# protoCtrl.net
KiCad netlist of a schematic drawn in EAGLE
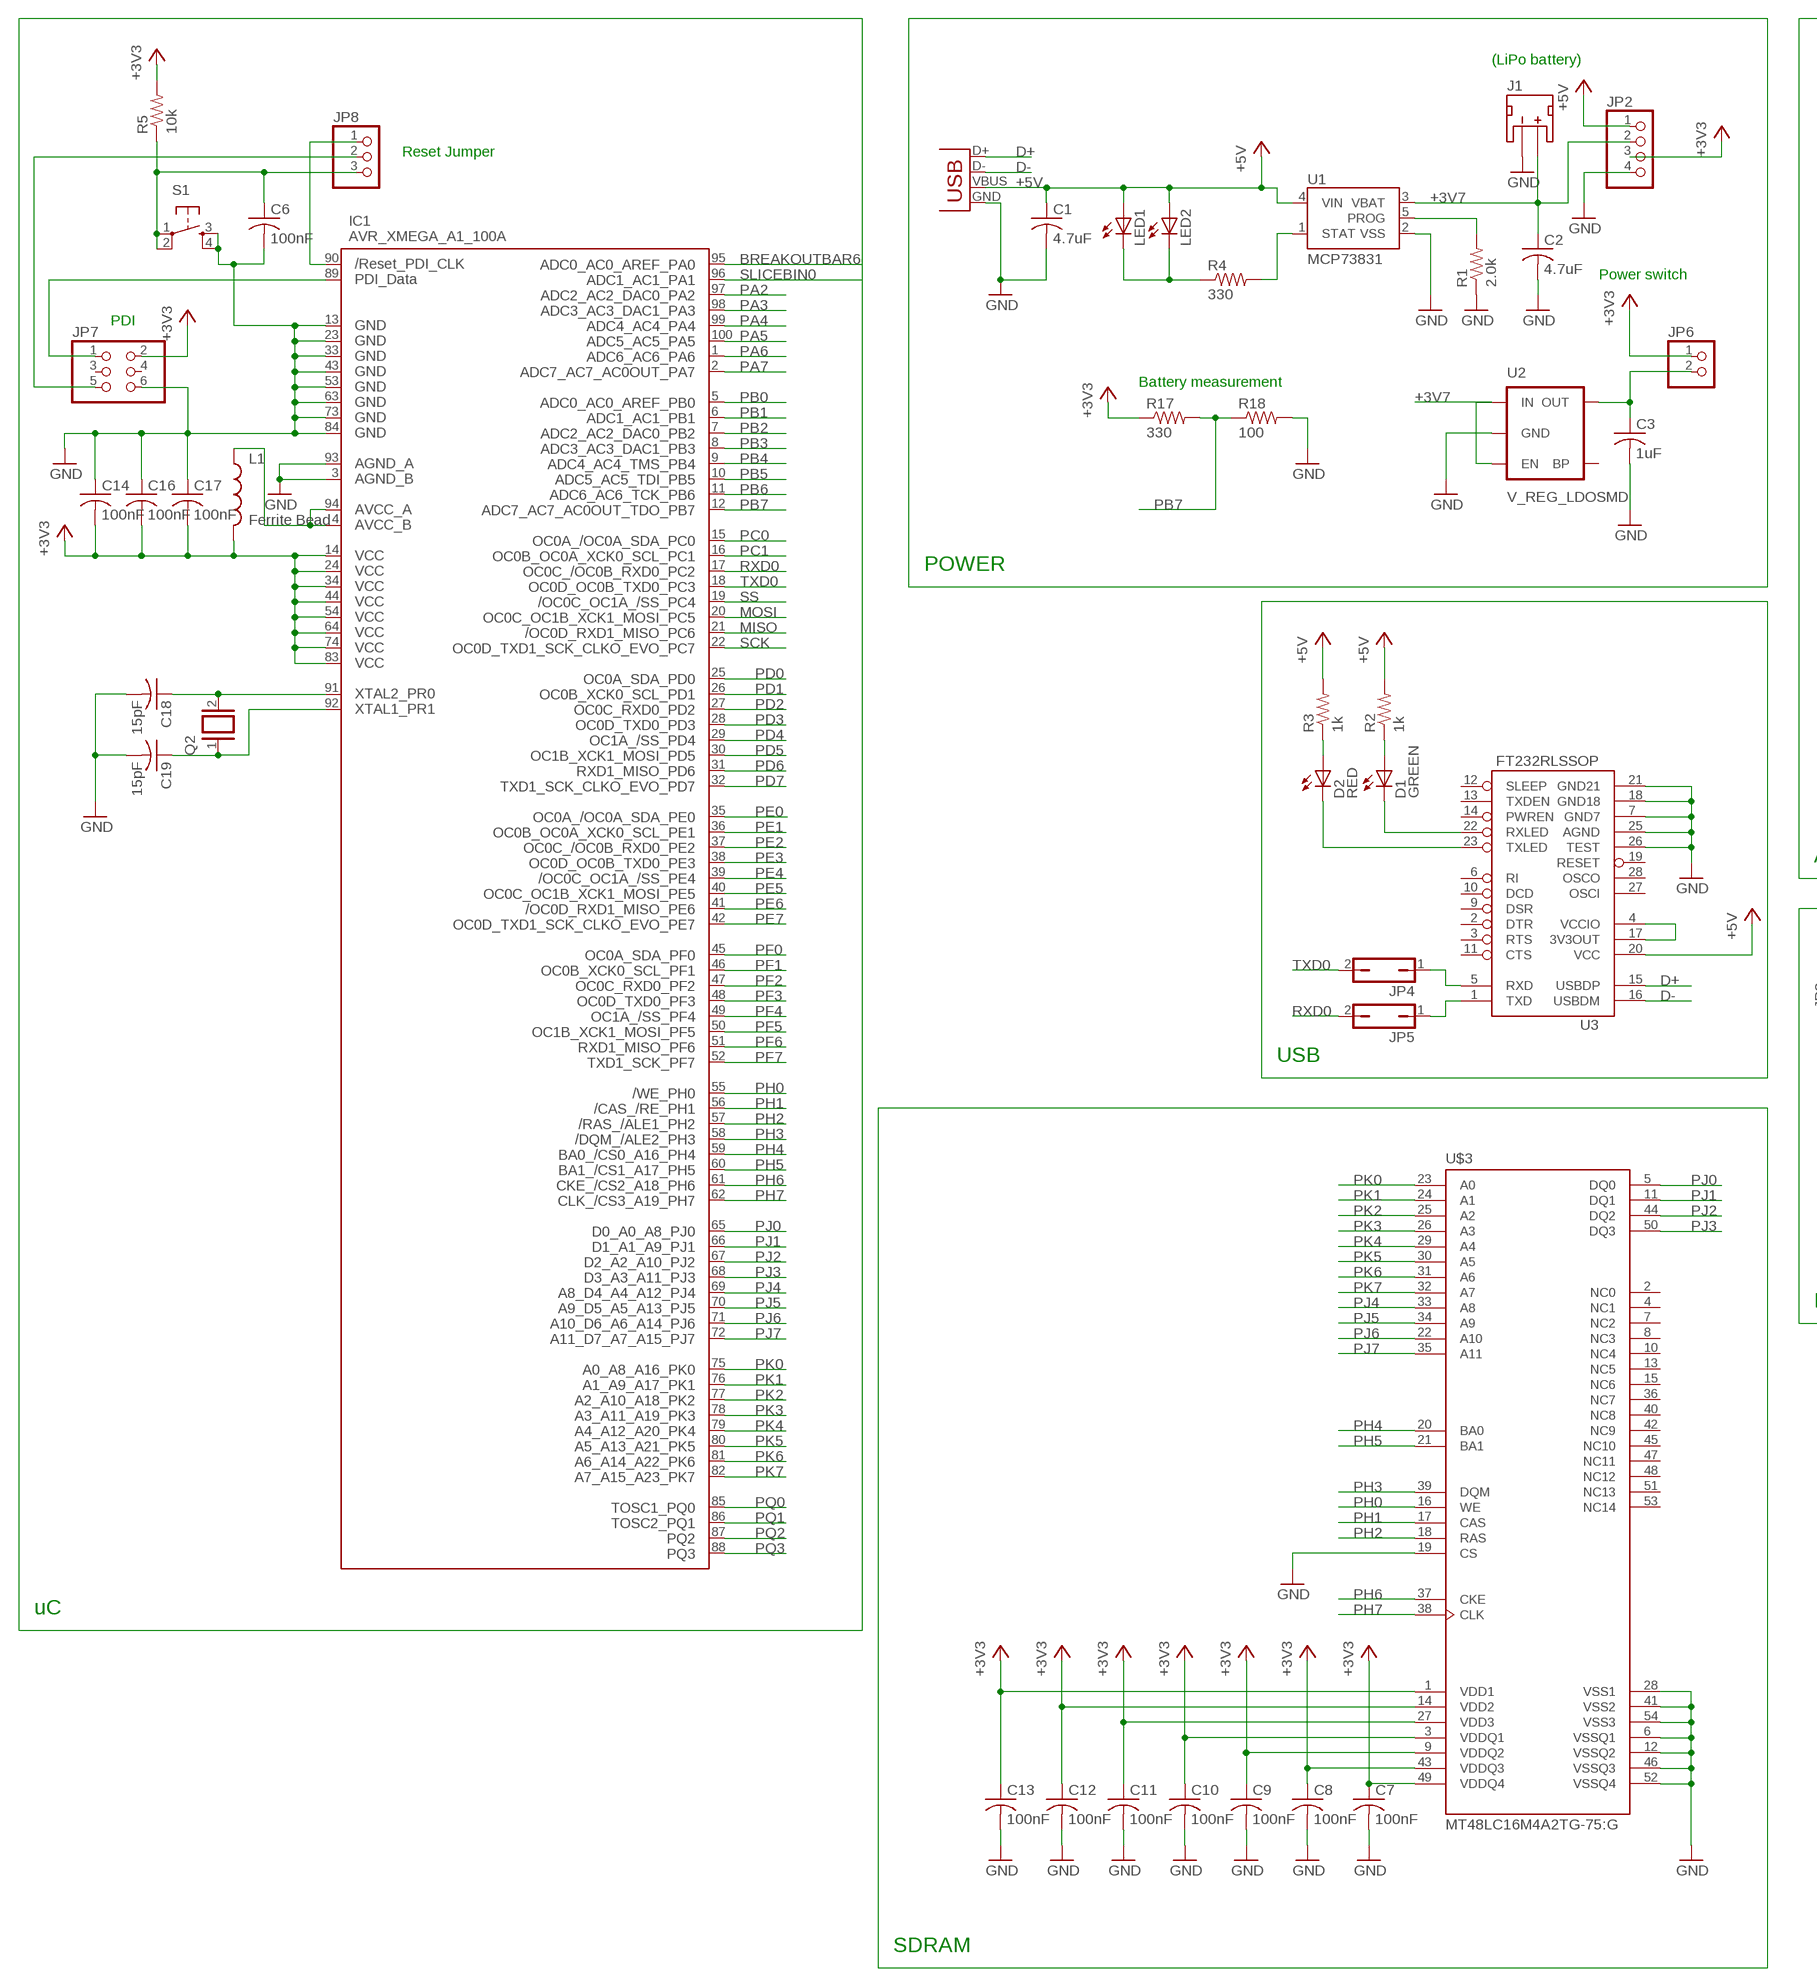
[diagram p0: schematic, sheet 1, part 1 of 2]
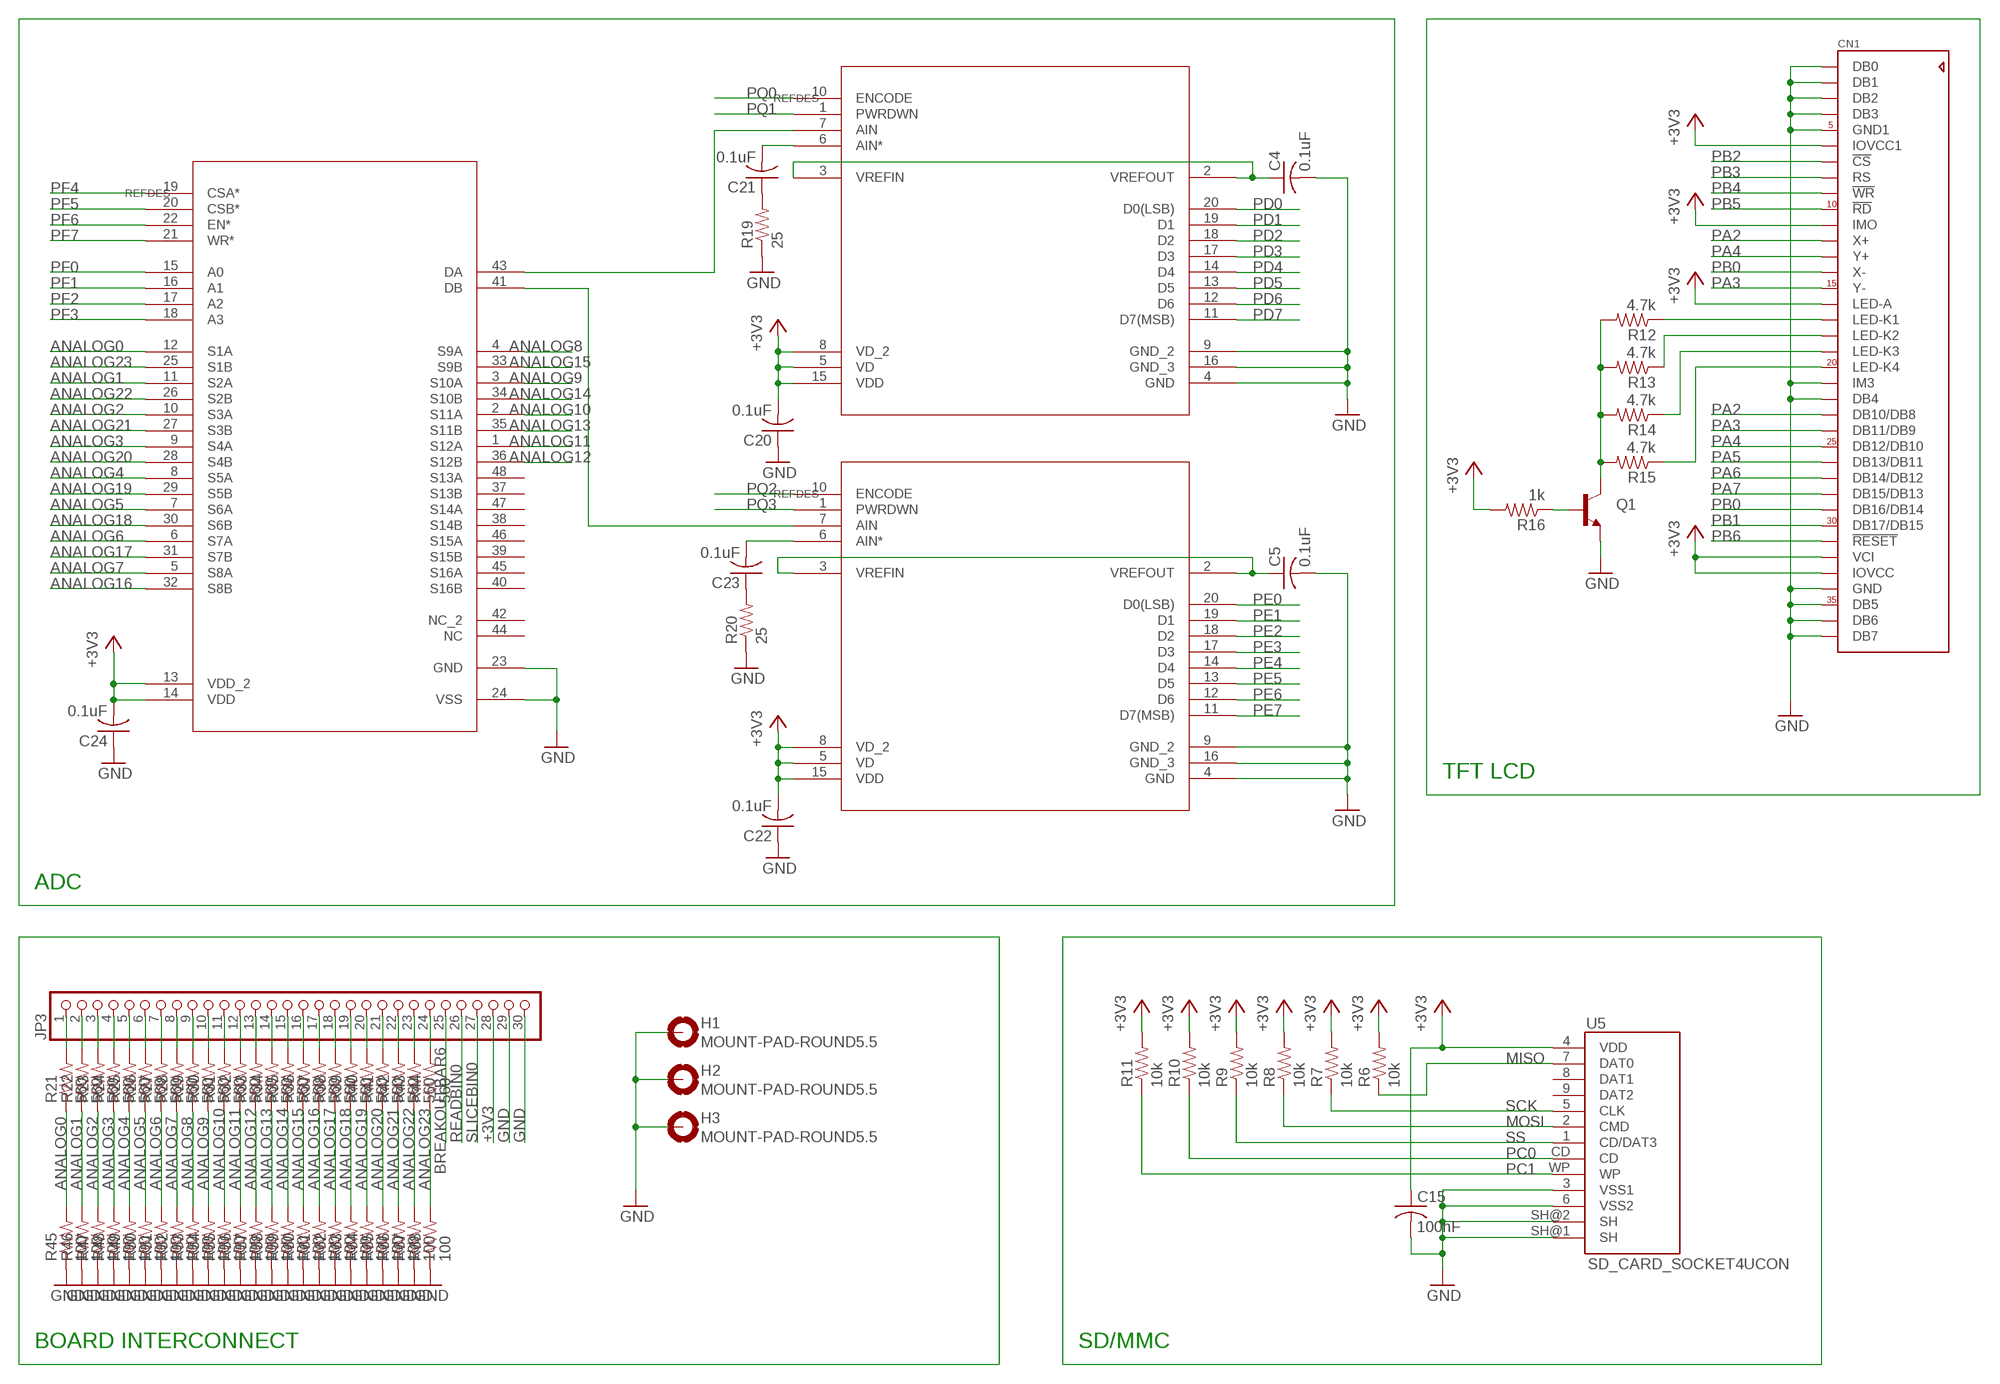
[diagram p1: schematic, sheet 1, part 2 of 2]

(export (version "E")
  (design (tool "Eeschema 10.0.6"))
  (components
    (comp (ref "C1")
      (value "4.7uF")
      (footprint "eagle-import:C0603")
      (libsource (lib "eagle-import") (part "C-USC0603"))
    )
    (comp (ref "C2")
      (value "4.7uF")
      (footprint "eagle-import:C0603")
      (libsource (lib "eagle-import") (part "C-USC0603"))
    )
    (comp (ref "C3")
      (value "1uF")
      (footprint "eagle-import:C0603")
      (libsource (lib "eagle-import") (part "C-USC0603"))
    )
    (comp (ref "C4")
      (value "0.1uF")
      (footprint "eagle-import:C0603")
      (libsource (lib "eagle-import") (part "C-USC0603"))
    )
    (comp (ref "C5")
      (value "0.1uF")
      (footprint "eagle-import:C0603")
      (libsource (lib "eagle-import") (part "C-USC0603"))
    )
    (comp (ref "C6")
      (value "100nF")
      (footprint "eagle-import:C0603")
      (libsource (lib "eagle-import") (part "C-USC0603"))
    )
    (comp (ref "C7")
      (value "100nF")
      (footprint "eagle-import:C0603")
      (libsource (lib "eagle-import") (part "C-USC0603"))
    )
    (comp (ref "C8")
      (value "100nF")
      (footprint "eagle-import:C0603")
      (libsource (lib "eagle-import") (part "C-USC0603"))
    )
    (comp (ref "C9")
      (value "100nF")
      (footprint "eagle-import:C0603")
      (libsource (lib "eagle-import") (part "C-USC0603"))
    )
    (comp (ref "C10")
      (value "100nF")
      (footprint "eagle-import:C0603")
      (libsource (lib "eagle-import") (part "C-USC0603"))
    )
    (comp (ref "C11")
      (value "100nF")
      (footprint "eagle-import:C0603")
      (libsource (lib "eagle-import") (part "C-USC0603"))
    )
    (comp (ref "C12")
      (value "100nF")
      (footprint "eagle-import:C0603")
      (libsource (lib "eagle-import") (part "C-USC0603"))
    )
    (comp (ref "C13")
      (value "100nF")
      (footprint "eagle-import:C0603")
      (libsource (lib "eagle-import") (part "C-USC0603"))
    )
    (comp (ref "C14")
      (value "100nF")
      (footprint "eagle-import:C0603")
      (libsource (lib "eagle-import") (part "C-USC0603"))
    )
    (comp (ref "C15")
      (value "100nF")
      (footprint "eagle-import:C0603")
      (libsource (lib "eagle-import") (part "C-USC0603"))
    )
    (comp (ref "C16")
      (value "100nF")
      (footprint "eagle-import:C0603")
      (libsource (lib "eagle-import") (part "C-USC0603"))
    )
    (comp (ref "C17")
      (value "100nF")
      (footprint "eagle-import:C0603")
      (libsource (lib "eagle-import") (part "C-USC0603"))
    )
    (comp (ref "C18")
      (value "15pF")
      (footprint "eagle-import:C0603")
      (libsource (lib "eagle-import") (part "resistor_C-USC0603"))
    )
    (comp (ref "C19")
      (value "15pF")
      (footprint "eagle-import:C0603")
      (libsource (lib "eagle-import") (part "resistor_C-USC0603"))
    )
    (comp (ref "C20")
      (value "0.1uF")
      (footprint "eagle-import:C0603")
      (libsource (lib "eagle-import") (part "C-USC0603"))
    )
    (comp (ref "C21")
      (value "0.1uF")
      (footprint "eagle-import:C0603")
      (libsource (lib "eagle-import") (part "C-USC0603"))
    )
    (comp (ref "C22")
      (value "0.1uF")
      (footprint "eagle-import:C0603")
      (libsource (lib "eagle-import") (part "C-USC0603"))
    )
    (comp (ref "C23")
      (value "0.1uF")
      (footprint "eagle-import:C0603")
      (libsource (lib "eagle-import") (part "C-USC0603"))
    )
    (comp (ref "C24")
      (value "0.1uF")
      (footprint "eagle-import:C0603")
      (libsource (lib "eagle-import") (part "C-USC0603"))
    )
    (comp (ref "CN1")
      (value "ILI9325_LCD1.0MM")
      (footprint "eagle-import:ILI9325_28INCH_TS")
      (libsource (lib "eagle-import") (part "ILI9325_LCD1.0MM"))
    )
    (comp (ref "D1")
      (value "GREEN")
      (footprint "eagle-import:LED-0603")
      (libsource (lib "eagle-import") (part "LED-GREEN0603"))
    )
    (comp (ref "D2")
      (value "RED")
      (footprint "eagle-import:LED-0603")
      (libsource (lib "eagle-import") (part "LED-RED0603"))
    )
    (comp (ref "H1")
      (value "MOUNT-PAD-ROUND5.5")
      (footprint "eagle-import:5,5-PAD")
      (libsource (lib "eagle-import") (part "MOUNT-PAD-ROUND5.5"))
    )
    (comp (ref "H2")
      (value "MOUNT-PAD-ROUND5.5")
      (footprint "eagle-import:5,5-PAD")
      (libsource (lib "eagle-import") (part "MOUNT-PAD-ROUND5.5"))
    )
    (comp (ref "H3")
      (value "MOUNT-PAD-ROUND5.5")
      (footprint "eagle-import:5,5-PAD")
      (libsource (lib "eagle-import") (part "MOUNT-PAD-ROUND5.5"))
    )
    (comp (ref "IC1")
      (value "AVR_XMEGA_A1_100A")
      (footprint "eagle-import:TQFP100")
      (libsource (lib "eagle-import") (part "AVR_XMEGA_A1_100A"))
    )
    (comp (ref "J1")
      (value "JST_2MM_MALE")
      (footprint "eagle-import:JST-2-SMD")
      (libsource (lib "eagle-import") (part "JST_2MM_MALE"))
    )
    (comp (ref "JP1")
      (value "USBSMD")
      (footprint "eagle-import:USB-MINIB")
      (libsource (lib "eagle-import") (part "USBSMD"))
    )
    (comp (ref "JP2")
      (value "PINHD-1X4")
      (footprint "eagle-import:1X04")
      (libsource (lib "eagle-import") (part "PINHD-1X4"))
    )
    (comp (ref "JP3")
      (value "PINHD-1X30")
      (footprint "eagle-import:1X30")
      (libsource (lib "eagle-import") (part "PINHD-1X30"))
    )
    (comp (ref "JP4")
      (value "JP1Q")
      (footprint "eagle-import:JP1")
      (libsource (lib "eagle-import") (part "JP1Q"))
    )
    (comp (ref "JP5")
      (value "JP1Q")
      (footprint "eagle-import:JP1")
      (libsource (lib "eagle-import") (part "JP1Q"))
    )
    (comp (ref "JP6")
      (value "PINHD-1X2")
      (footprint "eagle-import:1X02")
      (libsource (lib "eagle-import") (part "PINHD-1X2"))
    )
    (comp (ref "JP7")
      (value "PINHD-2X3")
      (footprint "eagle-import:2X03")
      (libsource (lib "eagle-import") (part "PINHD-2X3"))
    )
    (comp (ref "JP8")
      (value "PINHD-1X3")
      (footprint "eagle-import:1X03")
      (libsource (lib "eagle-import") (part "PINHD-1X3"))
    )
    (comp (ref "L1")
      (value "Ferrite Bead")
      (footprint "eagle-import:0603")
      (libsource (lib "eagle-import") (part "INDUCTOR0603"))
    )
    (comp (ref "LED1")
      (value "LED1206")
      (footprint "eagle-import:LED-1206")
      (libsource (lib "eagle-import") (part "LED1206"))
    )
    (comp (ref "LED2")
      (value "LED3MM")
      (footprint "eagle-import:LED3MM")
      (libsource (lib "eagle-import") (part "LED3MM"))
    )
    (comp (ref "Q1")
      (value "TRANSISTOR_NPN\"")
      (footprint "eagle-import:SOT223")
      (libsource (lib "eagle-import") (part "TRANSISTOR_NPN{dblquote}"))
    )
    (comp (ref "Q2")
      (value "XTAL/S")
      (footprint "eagle-import:QS")
      (libsource (lib "eagle-import") (part "XTAL/S"))
    )
    (comp (ref "R1")
      (value "2.0k")
      (footprint "eagle-import:0402-RES")
      (libsource (lib "eagle-import") (part "2.0KOHM1/10W5%(0603)"))
    )
    (comp (ref "R2")
      (value "1k")
      (footprint "eagle-import:0402-RES")
      (libsource (lib "eagle-import") (part "1K-1%"))
    )
    (comp (ref "R3")
      (value "1k")
      (footprint "eagle-import:0402-RES")
      (libsource (lib "eagle-import") (part "1K-1%"))
    )
    (comp (ref "R4")
      (value "330")
      (footprint "eagle-import:0402-RES")
      (libsource (lib "eagle-import") (part "330OHM1/10W1%(0603)"))
    )
    (comp (ref "R5")
      (value "10k")
      (footprint "eagle-import:0402-RES")
      (fields (field (name "PROD_ID") "RES-08296"))
      (libsource (lib "eagle-import") (part "2.0KOHM1/10W5%(0603)"))
    )
    (comp (ref "R6")
      (value "10k")
      (footprint "eagle-import:0402-RES")
      (fields (field (name "PROD_ID") "RES-08296"))
      (libsource (lib "eagle-import") (part "2.0KOHM1/10W5%(0603)"))
    )
    (comp (ref "R7")
      (value "10k")
      (footprint "eagle-import:0402-RES")
      (fields (field (name "PROD_ID") "RES-08296"))
      (libsource (lib "eagle-import") (part "2.0KOHM1/10W5%(0603)"))
    )
    (comp (ref "R8")
      (value "10k")
      (footprint "eagle-import:0402-RES")
      (fields (field (name "PROD_ID") "RES-08296"))
      (libsource (lib "eagle-import") (part "2.0KOHM1/10W5%(0603)"))
    )
    (comp (ref "R9")
      (value "10k")
      (footprint "eagle-import:0402-RES")
      (fields (field (name "PROD_ID") "RES-08296"))
      (libsource (lib "eagle-import") (part "2.0KOHM1/10W5%(0603)"))
    )
    (comp (ref "R10")
      (value "10k")
      (footprint "eagle-import:0402-RES")
      (fields (field (name "PROD_ID") "RES-08296"))
      (libsource (lib "eagle-import") (part "2.0KOHM1/10W5%(0603)"))
    )
    (comp (ref "R11")
      (value "10k")
      (footprint "eagle-import:0402-RES")
      (fields (field (name "PROD_ID") "RES-08296"))
      (libsource (lib "eagle-import") (part "2.0KOHM1/10W5%(0603)"))
    )
    (comp (ref "R12")
      (value "4.7k")
      (footprint "eagle-import:0402-RES")
      (fields (field (name "PROD_ID") "RES-08296"))
      (libsource (lib "eagle-import") (part "2.0KOHM1/10W5%(0603)"))
    )
    (comp (ref "R13")
      (value "4.7k")
      (footprint "eagle-import:0402-RES")
      (fields (field (name "PROD_ID") "RES-08296"))
      (libsource (lib "eagle-import") (part "2.0KOHM1/10W5%(0603)"))
    )
    (comp (ref "R14")
      (value "4.7k")
      (footprint "eagle-import:0402-RES")
      (fields (field (name "PROD_ID") "RES-08296"))
      (libsource (lib "eagle-import") (part "2.0KOHM1/10W5%(0603)"))
    )
    (comp (ref "R15")
      (value "4.7k")
      (footprint "eagle-import:0402-RES")
      (fields (field (name "PROD_ID") "RES-08296"))
      (libsource (lib "eagle-import") (part "2.0KOHM1/10W5%(0603)"))
    )
    (comp (ref "R16")
      (value "1k")
      (footprint "eagle-import:0402-RES")
      (fields (field (name "PROD_ID") "RES-08296"))
      (libsource (lib "eagle-import") (part "2.0KOHM1/10W5%(0603)"))
    )
    (comp (ref "R17")
      (value "330")
      (footprint "eagle-import:0402-RES")
      (fields (field (name "PROD_ID") "RES-00818"))
      (libsource (lib "eagle-import") (part "330OHM1/10W1%(0603)"))
    )
    (comp (ref "R18")
      (value "100")
      (footprint "eagle-import:0402-RES")
      (fields (field (name "PROD_ID") "RES-00818"))
      (libsource (lib "eagle-import") (part "330OHM1/10W1%(0603)"))
    )
    (comp (ref "R19")
      (value "25")
      (footprint "eagle-import:0402-RES")
      (fields (field (name "PROD_ID") "RES-00818"))
      (libsource (lib "eagle-import") (part "330OHM1/10W1%(0603)"))
    )
    (comp (ref "R20")
      (value "25")
      (footprint "eagle-import:0402-RES")
      (fields (field (name "PROD_ID") "RES-00818"))
      (libsource (lib "eagle-import") (part "330OHM1/10W1%(0603)"))
    )
    (comp (ref "R21")
      (value "560")
      (footprint "eagle-import:0402-RES")
      (fields (field (name "PROD_ID") "RES-00818"))
      (libsource (lib "eagle-import") (part "330OHM1/10W1%(0603)"))
    )
    (comp (ref "R22")
      (value "560")
      (footprint "eagle-import:0402-RES")
      (fields (field (name "PROD_ID") "RES-00818"))
      (libsource (lib "eagle-import") (part "330OHM1/10W1%(0603)"))
    )
    (comp (ref "R23")
      (value "560")
      (footprint "eagle-import:0402-RES")
      (fields (field (name "PROD_ID") "RES-00818"))
      (libsource (lib "eagle-import") (part "330OHM1/10W1%(0603)"))
    )
    (comp (ref "R24")
      (value "560")
      (footprint "eagle-import:0402-RES")
      (fields (field (name "PROD_ID") "RES-00818"))
      (libsource (lib "eagle-import") (part "330OHM1/10W1%(0603)"))
    )
    (comp (ref "R25")
      (value "560")
      (footprint "eagle-import:0402-RES")
      (fields (field (name "PROD_ID") "RES-00818"))
      (libsource (lib "eagle-import") (part "330OHM1/10W1%(0603)"))
    )
    (comp (ref "R26")
      (value "560")
      (footprint "eagle-import:0402-RES")
      (fields (field (name "PROD_ID") "RES-00818"))
      (libsource (lib "eagle-import") (part "330OHM1/10W1%(0603)"))
    )
    (comp (ref "R27")
      (value "560")
      (footprint "eagle-import:0402-RES")
      (fields (field (name "PROD_ID") "RES-00818"))
      (libsource (lib "eagle-import") (part "330OHM1/10W1%(0603)"))
    )
    (comp (ref "R28")
      (value "560")
      (footprint "eagle-import:0402-RES")
      (fields (field (name "PROD_ID") "RES-00818"))
      (libsource (lib "eagle-import") (part "330OHM1/10W1%(0603)"))
    )
    (comp (ref "R29")
      (value "560")
      (footprint "eagle-import:0402-RES")
      (fields (field (name "PROD_ID") "RES-00818"))
      (libsource (lib "eagle-import") (part "330OHM1/10W1%(0603)"))
    )
    (comp (ref "R30")
      (value "560")
      (footprint "eagle-import:0402-RES")
      (fields (field (name "PROD_ID") "RES-00818"))
      (libsource (lib "eagle-import") (part "330OHM1/10W1%(0603)"))
    )
    (comp (ref "R31")
      (value "560")
      (footprint "eagle-import:0402-RES")
      (fields (field (name "PROD_ID") "RES-00818"))
      (libsource (lib "eagle-import") (part "330OHM1/10W1%(0603)"))
    )
    (comp (ref "R32")
      (value "560")
      (footprint "eagle-import:0402-RES")
      (fields (field (name "PROD_ID") "RES-00818"))
      (libsource (lib "eagle-import") (part "330OHM1/10W1%(0603)"))
    )
    (comp (ref "R33")
      (value "560")
      (footprint "eagle-import:0402-RES")
      (fields (field (name "PROD_ID") "RES-00818"))
      (libsource (lib "eagle-import") (part "330OHM1/10W1%(0603)"))
    )
    (comp (ref "R34")
      (value "560")
      (footprint "eagle-import:0402-RES")
      (fields (field (name "PROD_ID") "RES-00818"))
      (libsource (lib "eagle-import") (part "330OHM1/10W1%(0603)"))
    )
    (comp (ref "R35")
      (value "560")
      (footprint "eagle-import:0402-RES")
      (fields (field (name "PROD_ID") "RES-00818"))
      (libsource (lib "eagle-import") (part "330OHM1/10W1%(0603)"))
    )
    (comp (ref "R36")
      (value "560")
      (footprint "eagle-import:0402-RES")
      (fields (field (name "PROD_ID") "RES-00818"))
      (libsource (lib "eagle-import") (part "330OHM1/10W1%(0603)"))
    )
    (comp (ref "R37")
      (value "560")
      (footprint "eagle-import:0402-RES")
      (fields (field (name "PROD_ID") "RES-00818"))
      (libsource (lib "eagle-import") (part "330OHM1/10W1%(0603)"))
    )
    (comp (ref "R38")
      (value "560")
      (footprint "eagle-import:0402-RES")
      (fields (field (name "PROD_ID") "RES-00818"))
      (libsource (lib "eagle-import") (part "330OHM1/10W1%(0603)"))
    )
    (comp (ref "R39")
      (value "560")
      (footprint "eagle-import:0402-RES")
      (fields (field (name "PROD_ID") "RES-00818"))
      (libsource (lib "eagle-import") (part "330OHM1/10W1%(0603)"))
    )
    (comp (ref "R40")
      (value "560")
      (footprint "eagle-import:0402-RES")
      (fields (field (name "PROD_ID") "RES-00818"))
      (libsource (lib "eagle-import") (part "330OHM1/10W1%(0603)"))
    )
    (comp (ref "R41")
      (value "560")
      (footprint "eagle-import:0402-RES")
      (fields (field (name "PROD_ID") "RES-00818"))
      (libsource (lib "eagle-import") (part "330OHM1/10W1%(0603)"))
    )
    (comp (ref "R42")
      (value "560")
      (footprint "eagle-import:0402-RES")
      (fields (field (name "PROD_ID") "RES-00818"))
      (libsource (lib "eagle-import") (part "330OHM1/10W1%(0603)"))
    )
    (comp (ref "R43")
      (value "560")
      (footprint "eagle-import:0402-RES")
      (fields (field (name "PROD_ID") "RES-00818"))
      (libsource (lib "eagle-import") (part "330OHM1/10W1%(0603)"))
    )
    (comp (ref "R44")
      (value "560")
      (footprint "eagle-import:0402-RES")
      (fields (field (name "PROD_ID") "RES-00818"))
      (libsource (lib "eagle-import") (part "330OHM1/10W1%(0603)"))
    )
    (comp (ref "R45")
      (value "100")
      (footprint "eagle-import:0402-RES")
      (fields (field (name "PROD_ID") "RES-00818"))
      (libsource (lib "eagle-import") (part "330OHM1/10W1%(0603)"))
    )
    (comp (ref "R46")
      (value "100")
      (footprint "eagle-import:0402-RES")
      (fields (field (name "PROD_ID") "RES-00818"))
      (libsource (lib "eagle-import") (part "330OHM1/10W1%(0603)"))
    )
    (comp (ref "R47")
      (value "100")
      (footprint "eagle-import:0402-RES")
      (fields (field (name "PROD_ID") "RES-00818"))
      (libsource (lib "eagle-import") (part "330OHM1/10W1%(0603)"))
    )
    (comp (ref "R48")
      (value "100")
      (footprint "eagle-import:0402-RES")
      (fields (field (name "PROD_ID") "RES-00818"))
      (libsource (lib "eagle-import") (part "330OHM1/10W1%(0603)"))
    )
    (comp (ref "R49")
      (value "100")
      (footprint "eagle-import:0402-RES")
      (fields (field (name "PROD_ID") "RES-00818"))
      (libsource (lib "eagle-import") (part "330OHM1/10W1%(0603)"))
    )
    (comp (ref "R50")
      (value "100")
      (footprint "eagle-import:0402-RES")
      (fields (field (name "PROD_ID") "RES-00818"))
      (libsource (lib "eagle-import") (part "330OHM1/10W1%(0603)"))
    )
    (comp (ref "R51")
      (value "100")
      (footprint "eagle-import:0402-RES")
      (fields (field (name "PROD_ID") "RES-00818"))
      (libsource (lib "eagle-import") (part "330OHM1/10W1%(0603)"))
    )
    (comp (ref "R52")
      (value "100")
      (footprint "eagle-import:0402-RES")
      (fields (field (name "PROD_ID") "RES-00818"))
      (libsource (lib "eagle-import") (part "330OHM1/10W1%(0603)"))
    )
    (comp (ref "R53")
      (value "100")
      (footprint "eagle-import:0402-RES")
      (fields (field (name "PROD_ID") "RES-00818"))
      (libsource (lib "eagle-import") (part "330OHM1/10W1%(0603)"))
    )
    (comp (ref "R54")
      (value "100")
      (footprint "eagle-import:0402-RES")
      (fields (field (name "PROD_ID") "RES-00818"))
      (libsource (lib "eagle-import") (part "330OHM1/10W1%(0603)"))
    )
    (comp (ref "R55")
      (value "100")
      (footprint "eagle-import:0402-RES")
      (fields (field (name "PROD_ID") "RES-00818"))
      (libsource (lib "eagle-import") (part "330OHM1/10W1%(0603)"))
    )
    (comp (ref "R56")
      (value "100")
      (footprint "eagle-import:0402-RES")
      (fields (field (name "PROD_ID") "RES-00818"))
      (libsource (lib "eagle-import") (part "330OHM1/10W1%(0603)"))
    )
    (comp (ref "R57")
      (value "100")
      (footprint "eagle-import:0402-RES")
      (fields (field (name "PROD_ID") "RES-00818"))
      (libsource (lib "eagle-import") (part "330OHM1/10W1%(0603)"))
    )
    (comp (ref "R58")
      (value "100")
      (footprint "eagle-import:0402-RES")
      (fields (field (name "PROD_ID") "RES-00818"))
      (libsource (lib "eagle-import") (part "330OHM1/10W1%(0603)"))
    )
    (comp (ref "R59")
      (value "100")
      (footprint "eagle-import:0402-RES")
      (fields (field (name "PROD_ID") "RES-00818"))
      (libsource (lib "eagle-import") (part "330OHM1/10W1%(0603)"))
    )
    (comp (ref "R60")
      (value "100")
      (footprint "eagle-import:0402-RES")
      (fields (field (name "PROD_ID") "RES-00818"))
      (libsource (lib "eagle-import") (part "330OHM1/10W1%(0603)"))
    )
    (comp (ref "R61")
      (value "100")
      (footprint "eagle-import:0402-RES")
      (fields (field (name "PROD_ID") "RES-00818"))
      (libsource (lib "eagle-import") (part "330OHM1/10W1%(0603)"))
    )
    (comp (ref "R62")
      (value "100")
      (footprint "eagle-import:0402-RES")
      (fields (field (name "PROD_ID") "RES-00818"))
      (libsource (lib "eagle-import") (part "330OHM1/10W1%(0603)"))
    )
    (comp (ref "R63")
      (value "100")
      (footprint "eagle-import:0402-RES")
      (fields (field (name "PROD_ID") "RES-00818"))
      (libsource (lib "eagle-import") (part "330OHM1/10W1%(0603)"))
    )
    (comp (ref "R64")
      (value "100")
      (footprint "eagle-import:0402-RES")
      (fields (field (name "PROD_ID") "RES-00818"))
      (libsource (lib "eagle-import") (part "330OHM1/10W1%(0603)"))
    )
    (comp (ref "R65")
      (value "100")
      (footprint "eagle-import:0402-RES")
      (fields (field (name "PROD_ID") "RES-00818"))
      (libsource (lib "eagle-import") (part "330OHM1/10W1%(0603)"))
    )
    (comp (ref "R66")
      (value "100")
      (footprint "eagle-import:0402-RES")
      (fields (field (name "PROD_ID") "RES-00818"))
      (libsource (lib "eagle-import") (part "330OHM1/10W1%(0603)"))
    )
    (comp (ref "R67")
      (value "100")
      (footprint "eagle-import:0402-RES")
      (fields (field (name "PROD_ID") "RES-00818"))
      (libsource (lib "eagle-import") (part "330OHM1/10W1%(0603)"))
    )
    (comp (ref "R68")
      (value "100")
      (footprint "eagle-import:0402-RES")
      (fields (field (name "PROD_ID") "RES-00818"))
      (libsource (lib "eagle-import") (part "330OHM1/10W1%(0603)"))
    )
    (comp (ref "S1")
      (value "TAC_SWITCHPTH")
      (footprint "eagle-import:TACTILE-PTH")
      (libsource (lib "eagle-import") (part "TAC_SWITCHPTH"))
    )
    (comp (ref "U$3")
      (value "MT48LC16M4A2TG-75:G")
      (footprint "eagle-import:TSOP54-400")
      (libsource (lib "eagle-import") (part "MT48LC16M4A2TG-75{colon}G"))
    )
    (comp (ref "U1")
      (value "MCP73831")
      (footprint "eagle-import:SOT23-5")
      (libsource (lib "eagle-import") (part "MCP73831"))
    )
    (comp (ref "U2")
      (value "V_REG_LDOSMD")
      (footprint "eagle-import:SOT23-5")
      (libsource (lib "eagle-import") (part "V_REG_LDOSMD"))
    )
    (comp (ref "U3")
      (value "FT232RLSSOP")
      (footprint "eagle-import:SSOP28DB")
      (libsource (lib "eagle-import") (part "FT232RLSSOP"))
    )
    (comp (ref "U4")
      (value "ADG726BSUZ")
      (footprint "eagle-import:SU_48")
      (libsource (lib "eagle-import") (part "ADG726BSUZ"))
    )
    (comp (ref "U5")
      (value "SD_CARD_SOCKET4UCON")
      (footprint "eagle-import:SDCARD_4UCONN")
      (libsource (lib "eagle-import") (part "SD_CARD_SOCKET4UCON"))
    )
    (comp (ref "U6")
      (value "AD9283BRSZ-80REAL")
      (footprint "eagle-import:SSOP20")
      (libsource (lib "eagle-import") (part "AD9283BRSZ-80REAL"))
    )
    (comp (ref "U7")
      (value "AD9283BRSZ-80REAL")
      (footprint "eagle-import:SSOP20")
      (libsource (lib "eagle-import") (part "AD9283BRSZ-80REAL"))
    )
  )
  (nets
    (net (code "1") (name "+3V3") (class "Default")
      (node (ref "C10") (pin "1") (pinfunction "1_1") (pintype "passive"))
      (node (ref "C11") (pin "1") (pinfunction "1_1") (pintype "passive"))
      (node (ref "C12") (pin "1") (pinfunction "1_1") (pintype "passive"))
      (node (ref "C13") (pin "1") (pinfunction "1_1") (pintype "passive"))
      (node (ref "C14") (pin "2") (pinfunction "2_2") (pintype "passive"))
      (node (ref "C15") (pin "1") (pinfunction "1_1") (pintype "passive"))
      (node (ref "C16") (pin "2") (pinfunction "2_2") (pintype "passive"))
      (node (ref "C17") (pin "2") (pinfunction "2_2") (pintype "passive"))
      (node (ref "C20") (pin "2") (pinfunction "2_2") (pintype "passive"))
      (node (ref "C22") (pin "2") (pinfunction "2_2") (pintype "passive"))
      (node (ref "C24") (pin "2") (pinfunction "2_2") (pintype "passive"))
      (node (ref "C7") (pin "1") (pinfunction "1_1") (pintype "passive"))
      (node (ref "C8") (pin "1") (pinfunction "1_1") (pintype "passive"))
      (node (ref "C9") (pin "1") (pinfunction "1_1") (pintype "passive"))
      (node (ref "CN1") (pin "11") (pinfunction "IMO_11") (pintype "passive"))
      (node (ref "CN1") (pin "16") (pinfunction "LED-A_16") (pintype "passive"))
      (node (ref "CN1") (pin "32") (pinfunction "VCI_32") (pintype "power_in"))
      (node (ref "CN1") (pin "33") (pinfunction "IOVCC_33") (pintype "power_in"))
      (node (ref "CN1") (pin "6") (pinfunction "IOVCC1_6") (pintype "power_in"))
      (node (ref "IC1") (pin "14") (pinfunction "VCC1_14") (pintype "bidirectional"))
      (node (ref "IC1") (pin "24") (pinfunction "VCC2_24") (pintype "bidirectional"))
      (node (ref "IC1") (pin "34") (pinfunction "VCC3_34") (pintype "bidirectional"))
      (node (ref "IC1") (pin "44") (pinfunction "VCC4_44") (pintype "bidirectional"))
      (node (ref "IC1") (pin "54") (pinfunction "VCC5_54") (pintype "bidirectional"))
      (node (ref "IC1") (pin "64") (pinfunction "VCC6_64") (pintype "bidirectional"))
      (node (ref "IC1") (pin "74") (pinfunction "VCC7_74") (pintype "bidirectional"))
      (node (ref "IC1") (pin "83") (pinfunction "VCC8_83") (pintype "bidirectional"))
      (node (ref "JP2") (pin "3") (pinfunction "3_3") (pintype "passive"))
      (node (ref "JP3") (pin "28") (pinfunction "28_28") (pintype "passive"))
      (node (ref "JP6") (pin "1") (pinfunction "1_1") (pintype "passive"))
      (node (ref "JP7") (pin "2") (pinfunction "2_2") (pintype "passive"))
      (node (ref "L1") (pin "2") (pinfunction "2_2") (pintype "passive"))
      (node (ref "R10") (pin "2") (pinfunction "2_2") (pintype "passive"))
      (node (ref "R11") (pin "2") (pinfunction "2_2") (pintype "passive"))
      (node (ref "R16") (pin "2") (pinfunction "2_2") (pintype "passive"))
      (node (ref "R17") (pin "1") (pinfunction "1_1") (pintype "passive"))
      (node (ref "R5") (pin "2") (pinfunction "2_2") (pintype "passive"))
      (node (ref "R6") (pin "2") (pinfunction "2_2") (pintype "passive"))
      (node (ref "R7") (pin "2") (pinfunction "2_2") (pintype "passive"))
      (node (ref "R8") (pin "2") (pinfunction "2_2") (pintype "passive"))
      (node (ref "R9") (pin "2") (pinfunction "2_2") (pintype "passive"))
      (node (ref "U$3") (pin "1") (pinfunction "VDD1_1") (pintype "power_in"))
      (node (ref "U$3") (pin "14") (pinfunction "VDD2_14") (pintype "power_in"))
      (node (ref "U$3") (pin "27") (pinfunction "VDD3_27") (pintype "power_in"))
      (node (ref "U$3") (pin "3") (pinfunction "VDDQ1_3") (pintype "power_in"))
      (node (ref "U$3") (pin "43") (pinfunction "VDDQ3_43") (pintype "power_in"))
      (node (ref "U$3") (pin "49") (pinfunction "VDDQ4_49") (pintype "power_in"))
      (node (ref "U$3") (pin "9") (pinfunction "VDDQ2_9") (pintype "power_in"))
      (node (ref "U4") (pin "13") (pinfunction "VDD_2_13") (pintype "passive"))
      (node (ref "U4") (pin "14") (pinfunction "VDD_14") (pintype "passive"))
      (node (ref "U5") (pin "4") (pinfunction "VDD_4") (pintype "power_in"))
      (node (ref "U6") (pin "15") (pinfunction "VDD_15") (pintype "passive"))
      (node (ref "U6") (pin "5") (pinfunction "VD_5") (pintype "passive"))
      (node (ref "U6") (pin "8") (pinfunction "VD_2_8") (pintype "passive"))
      (node (ref "U7") (pin "15") (pinfunction "VDD_15") (pintype "passive"))
      (node (ref "U7") (pin "5") (pinfunction "VD_5") (pintype "passive"))
      (node (ref "U7") (pin "8") (pinfunction "VD_2_8") (pintype "passive"))
    )
    (net (code "2") (name "+5V") (class "Default")
      (node (ref "C1") (pin "1") (pinfunction "1_1") (pintype "passive"))
      (node (ref "JP1") (pin "VBUS") (pinfunction "VBUS_VBUS") (pintype "bidirectional"))
      (node (ref "JP2") (pin "1") (pinfunction "1_1") (pintype "passive"))
      (node (ref "LED1") (pin "A") (pinfunction "A_A") (pintype "passive"))
      (node (ref "LED2") (pin "A") (pinfunction "A_A") (pintype "passive"))
      (node (ref "R2") (pin "2") (pinfunction "2_2") (pintype "passive"))
      (node (ref "R3") (pin "2") (pinfunction "2_2") (pintype "passive"))
      (node (ref "U1") (pin "4") (pinfunction "VIN_4") (pintype "power_in"))
      (node (ref "U3") (pin "20") (pinfunction "VCC_20") (pintype "power_in"))
    )
    (net (code "3") (name "/+3V7") (class "Default")
      (node (ref "C2") (pin "1") (pinfunction "1_1") (pintype "passive"))
      (node (ref "J1") (pin "2") (pinfunction "+_2") (pintype "bidirectional"))
      (node (ref "JP2") (pin "2") (pinfunction "2_2") (pintype "passive"))
      (node (ref "U1") (pin "3") (pinfunction "VBAT_3") (pintype "power_in"))
      (node (ref "U2") (pin "1") (pinfunction "IN_1") (pintype "input"))
      (node (ref "U2") (pin "3") (pinfunction "EN_3") (pintype "input"))
    )
    (net (code "4") (name "/ANALOG0") (class "Default")
      (node (ref "R21") (pin "1") (pinfunction "1_1") (pintype "passive"))
      (node (ref "R45") (pin "2") (pinfunction "2_2") (pintype "passive"))
      (node (ref "U4") (pin "12") (pinfunction "S1A_12") (pintype "passive"))
    )
    (net (code "5") (name "/ANALOG1") (class "Default")
      (node (ref "R22") (pin "1") (pinfunction "1_1") (pintype "passive"))
      (node (ref "R46") (pin "2") (pinfunction "2_2") (pintype "passive"))
      (node (ref "U4") (pin "11") (pinfunction "S2A_11") (pintype "passive"))
    )
    (net (code "6") (name "/ANALOG2") (class "Default")
      (node (ref "R23") (pin "1") (pinfunction "1_1") (pintype "passive"))
      (node (ref "R47") (pin "2") (pinfunction "2_2") (pintype "passive"))
      (node (ref "U4") (pin "10") (pinfunction "S3A_10") (pintype "passive"))
    )
    (net (code "7") (name "/ANALOG3") (class "Default")
      (node (ref "R24") (pin "1") (pinfunction "1_1") (pintype "passive"))
      (node (ref "R48") (pin "2") (pinfunction "2_2") (pintype "passive"))
      (node (ref "U4") (pin "9") (pinfunction "S4A_9") (pintype "passive"))
    )
    (net (code "8") (name "/ANALOG4") (class "Default")
      (node (ref "R25") (pin "1") (pinfunction "1_1") (pintype "passive"))
      (node (ref "R49") (pin "2") (pinfunction "2_2") (pintype "passive"))
      (node (ref "U4") (pin "8") (pinfunction "S5A_8") (pintype "passive"))
    )
    (net (code "9") (name "/ANALOG5") (class "Default")
      (node (ref "R26") (pin "1") (pinfunction "1_1") (pintype "passive"))
      (node (ref "R50") (pin "2") (pinfunction "2_2") (pintype "passive"))
      (node (ref "U4") (pin "7") (pinfunction "S6A_7") (pintype "passive"))
    )
    (net (code "10") (name "/ANALOG6") (class "Default")
      (node (ref "R27") (pin "1") (pinfunction "1_1") (pintype "passive"))
      (node (ref "R51") (pin "2") (pinfunction "2_2") (pintype "passive"))
      (node (ref "U4") (pin "6") (pinfunction "S7A_6") (pintype "passive"))
    )
    (net (code "11") (name "/ANALOG7") (class "Default")
      (node (ref "R28") (pin "1") (pinfunction "1_1") (pintype "passive"))
      (node (ref "R52") (pin "2") (pinfunction "2_2") (pintype "passive"))
      (node (ref "U4") (pin "5") (pinfunction "S8A_5") (pintype "passive"))
    )
    (net (code "12") (name "/ANALOG8") (class "Default")
      (node (ref "R29") (pin "1") (pinfunction "1_1") (pintype "passive"))
      (node (ref "R53") (pin "2") (pinfunction "2_2") (pintype "passive"))
      (node (ref "U4") (pin "4") (pinfunction "S9A_4") (pintype "passive"))
    )
    (net (code "13") (name "/ANALOG9") (class "Default")
      (node (ref "R30") (pin "1") (pinfunction "1_1") (pintype "passive"))
      (node (ref "R54") (pin "2") (pinfunction "2_2") (pintype "passive"))
      (node (ref "U4") (pin "3") (pinfunction "S10A_3") (pintype "passive"))
    )
    (net (code "14") (name "/ANALOG10") (class "Default")
      (node (ref "R31") (pin "1") (pinfunction "1_1") (pintype "passive"))
      (node (ref "R55") (pin "2") (pinfunction "2_2") (pintype "passive"))
      (node (ref "U4") (pin "2") (pinfunction "S11A_2") (pintype "passive"))
    )
    (net (code "15") (name "/ANALOG11") (class "Default")
      (node (ref "R32") (pin "1") (pinfunction "1_1") (pintype "passive"))
      (node (ref "R56") (pin "2") (pinfunction "2_2") (pintype "passive"))
      (node (ref "U4") (pin "1") (pinfunction "S12A_1") (pintype "passive"))
    )
    (net (code "16") (name "/ANALOG12") (class "Default")
      (node (ref "R33") (pin "1") (pinfunction "1_1") (pintype "passive"))
      (node (ref "R57") (pin "2") (pinfunction "2_2") (pintype "passive"))
      (node (ref "U4") (pin "36") (pinfunction "S12B_36") (pintype "passive"))
    )
    (net (code "17") (name "/ANALOG13") (class "Default")
      (node (ref "R34") (pin "1") (pinfunction "1_1") (pintype "passive"))
      (node (ref "R58") (pin "2") (pinfunction "2_2") (pintype "passive"))
      (node (ref "U4") (pin "35") (pinfunction "S11B_35") (pintype "passive"))
    )
    (net (code "18") (name "/ANALOG14") (class "Default")
      (node (ref "R35") (pin "1") (pinfunction "1_1") (pintype "passive"))
      (node (ref "R59") (pin "2") (pinfunction "2_2") (pintype "passive"))
      (node (ref "U4") (pin "34") (pinfunction "S10B_34") (pintype "passive"))
    )
    (net (code "19") (name "/ANALOG15") (class "Default")
      (node (ref "R36") (pin "1") (pinfunction "1_1") (pintype "passive"))
      (node (ref "R60") (pin "2") (pinfunction "2_2") (pintype "passive"))
      (node (ref "U4") (pin "33") (pinfunction "S9B_33") (pintype "passive"))
    )
    (net (code "20") (name "/ANALOG16") (class "Default")
      (node (ref "R37") (pin "1") (pinfunction "1_1") (pintype "passive"))
      (node (ref "R61") (pin "2") (pinfunction "2_2") (pintype "passive"))
      (node (ref "U4") (pin "32") (pinfunction "S8B_32") (pintype "passive"))
    )
    (net (code "21") (name "/ANALOG17") (class "Default")
      (node (ref "R38") (pin "1") (pinfunction "1_1") (pintype "passive"))
      (node (ref "R62") (pin "2") (pinfunction "2_2") (pintype "passive"))
      (node (ref "U4") (pin "31") (pinfunction "S7B_31") (pintype "passive"))
    )
    (net (code "22") (name "/ANALOG18") (class "Default")
      (node (ref "R39") (pin "1") (pinfunction "1_1") (pintype "passive"))
      (node (ref "R63") (pin "2") (pinfunction "2_2") (pintype "passive"))
      (node (ref "U4") (pin "30") (pinfunction "S6B_30") (pintype "passive"))
    )
    (net (code "23") (name "/ANALOG19") (class "Default")
      (node (ref "R40") (pin "1") (pinfunction "1_1") (pintype "passive"))
      (node (ref "R64") (pin "2") (pinfunction "2_2") (pintype "passive"))
      (node (ref "U4") (pin "29") (pinfunction "S5B_29") (pintype "passive"))
    )
    (net (code "24") (name "/ANALOG20") (class "Default")
      (node (ref "R41") (pin "1") (pinfunction "1_1") (pintype "passive"))
      (node (ref "R65") (pin "2") (pinfunction "2_2") (pintype "passive"))
      (node (ref "U4") (pin "28") (pinfunction "S4B_28") (pintype "passive"))
    )
    (net (code "25") (name "/ANALOG21") (class "Default")
      (node (ref "R42") (pin "1") (pinfunction "1_1") (pintype "passive"))
      (node (ref "R66") (pin "2") (pinfunction "2_2") (pintype "passive"))
      (node (ref "U4") (pin "27") (pinfunction "S3B_27") (pintype "passive"))
    )
    (net (code "26") (name "/ANALOG22") (class "Default")
      (node (ref "R43") (pin "1") (pinfunction "1_1") (pintype "passive"))
      (node (ref "R67") (pin "2") (pinfunction "2_2") (pintype "passive"))
      (node (ref "U4") (pin "26") (pinfunction "S2B_26") (pintype "passive"))
    )
    (net (code "27") (name "/ANALOG23") (class "Default")
      (node (ref "R44") (pin "1") (pinfunction "1_1") (pintype "passive"))
      (node (ref "R68") (pin "2") (pinfunction "2_2") (pintype "passive"))
      (node (ref "U4") (pin "25") (pinfunction "S1B_25") (pintype "passive"))
    )
    (net (code "28") (name "/BREAKOUTBAR6") (class "Default")
      (node (ref "IC1") (pin "95") (pinfunction "PA0_95") (pintype "bidirectional"))
      (node (ref "JP3") (pin "25") (pinfunction "25_25") (pintype "passive"))
    )
    (net (code "29") (name "/D+") (class "Default")
      (node (ref "JP1") (pin "D+") (pinfunction "D+_D+") (pintype "bidirectional"))
      (node (ref "U3") (pin "15") (pinfunction "USBDP_15") (pintype "bidirectional"))
    )
    (net (code "30") (name "/D-") (class "Default")
      (node (ref "JP1") (pin "D-") (pinfunction "D-_D-") (pintype "bidirectional"))
      (node (ref "U3") (pin "16") (pinfunction "USBDM_16") (pintype "bidirectional"))
    )
    (net (code "31") (name "/MISO") (class "Default")
      (node (ref "IC1") (pin "21") (pinfunction "PC6_21") (pintype "bidirectional"))
      (node (ref "R6") (pin "1") (pinfunction "1_1") (pintype "passive"))
      (node (ref "U5") (pin "7") (pinfunction "DAT0_7") (pintype "bidirectional"))
    )
    (net (code "32") (name "/MOSI") (class "Default")
      (node (ref "IC1") (pin "20") (pinfunction "PC5_20") (pintype "bidirectional"))
      (node (ref "R8") (pin "1") (pinfunction "1_1") (pintype "passive"))
      (node (ref "U5") (pin "2") (pinfunction "CMD_2") (pintype "bidirectional"))
    )
    (net (code "33") (name "/PA2") (class "Default")
      (node (ref "CN1") (pin "12") (pinfunction "X+_12") (pintype "passive"))
      (node (ref "CN1") (pin "23") (pinfunction "DB10/DB8_23") (pintype "passive"))
      (node (ref "IC1") (pin "97") (pinfunction "PA2_97") (pintype "bidirectional"))
    )
    (net (code "34") (name "/PA3") (class "Default")
      (node (ref "CN1") (pin "15") (pinfunction "Y-_15") (pintype "passive"))
      (node (ref "CN1") (pin "24") (pinfunction "DB11/DB9_24") (pintype "passive"))
      (node (ref "IC1") (pin "98") (pinfunction "PA3_98") (pintype "bidirectional"))
    )
    (net (code "35") (name "/PA4") (class "Default")
      (node (ref "CN1") (pin "13") (pinfunction "Y+_13") (pintype "passive"))
      (node (ref "CN1") (pin "25") (pinfunction "DB12/DB10_25") (pintype "passive"))
      (node (ref "IC1") (pin "99") (pinfunction "PA4_99") (pintype "bidirectional"))
    )
    (net (code "36") (name "/PA5") (class "Default")
      (node (ref "CN1") (pin "26") (pinfunction "DB13/DB11_26") (pintype "passive"))
      (node (ref "IC1") (pin "100") (pinfunction "PA5_100") (pintype "bidirectional"))
    )
    (net (code "37") (name "/PA6") (class "Default")
      (node (ref "CN1") (pin "27") (pinfunction "DB14/DB12_27") (pintype "passive"))
      (node (ref "IC1") (pin "1") (pinfunction "PA6_1") (pintype "bidirectional"))
    )
    (net (code "38") (name "/PA7") (class "Default")
      (node (ref "CN1") (pin "28") (pinfunction "DB15/DB13_28") (pintype "passive"))
      (node (ref "IC1") (pin "2") (pinfunction "PA7_2") (pintype "bidirectional"))
    )
    (net (code "39") (name "/PB0") (class "Default")
      (node (ref "CN1") (pin "14") (pinfunction "X-_14") (pintype "passive"))
      (node (ref "CN1") (pin "29") (pinfunction "DB16/DB14_29") (pintype "passive"))
      (node (ref "IC1") (pin "5") (pinfunction "PB0_5") (pintype "bidirectional"))
    )
    (net (code "40") (name "/PB1") (class "Default")
      (node (ref "CN1") (pin "30") (pinfunction "DB17/DB15_30") (pintype "passive"))
      (node (ref "IC1") (pin "6") (pinfunction "PB1_6") (pintype "bidirectional"))
    )
    (net (code "41") (name "/PB2") (class "Default")
      (node (ref "CN1") (pin "7") (pinfunction "~{CS}_7") (pintype "passive"))
      (node (ref "IC1") (pin "7") (pinfunction "PB2_7") (pintype "bidirectional"))
    )
    (net (code "42") (name "/PB3") (class "Default")
      (node (ref "CN1") (pin "8") (pinfunction "RS_8") (pintype "passive"))
      (node (ref "IC1") (pin "8") (pinfunction "PB3_8") (pintype "bidirectional"))
    )
    (net (code "43") (name "/PB4") (class "Default")
      (node (ref "CN1") (pin "9") (pinfunction "~{WR}_9") (pintype "passive"))
      (node (ref "IC1") (pin "9") (pinfunction "PB4_9") (pintype "bidirectional"))
    )
    (net (code "44") (name "/PB5") (class "Default")
      (node (ref "CN1") (pin "10") (pinfunction "~{RD}_10") (pintype "passive"))
      (node (ref "IC1") (pin "10") (pinfunction "PB5_10") (pintype "bidirectional"))
    )
    (net (code "45") (name "/PB6") (class "Default")
      (node (ref "CN1") (pin "31") (pinfunction "~{RESET}_31") (pintype "passive"))
      (node (ref "IC1") (pin "11") (pinfunction "PB6_11") (pintype "bidirectional"))
    )
    (net (code "46") (name "/PB7") (class "Default")
      (node (ref "IC1") (pin "12") (pinfunction "PB7_12") (pintype "bidirectional"))
      (node (ref "R17") (pin "2") (pinfunction "2_2") (pintype "passive"))
      (node (ref "R18") (pin "1") (pinfunction "1_1") (pintype "passive"))
    )
    (net (code "47") (name "/PC0") (class "Default")
      (node (ref "IC1") (pin "15") (pinfunction "PC0_15") (pintype "bidirectional"))
      (node (ref "R10") (pin "1") (pinfunction "1_1") (pintype "passive"))
      (node (ref "U5") (pin "CD") (pinfunction "CD_CD") (pintype "bidirectional"))
    )
    (net (code "48") (name "/PC1") (class "Default")
      (node (ref "IC1") (pin "16") (pinfunction "PC1_16") (pintype "bidirectional"))
      (node (ref "R11") (pin "1") (pinfunction "1_1") (pintype "passive"))
      (node (ref "U5") (pin "WP") (pinfunction "WP_WP") (pintype "bidirectional"))
    )
    (net (code "49") (name "/PD0") (class "Default")
      (node (ref "IC1") (pin "25") (pinfunction "PD0_25") (pintype "bidirectional"))
      (node (ref "U6") (pin "20") (pinfunction "D0(LSB)_20") (pintype "passive"))
    )
    (net (code "50") (name "/PD1") (class "Default")
      (node (ref "IC1") (pin "26") (pinfunction "PD1_26") (pintype "bidirectional"))
      (node (ref "U6") (pin "19") (pinfunction "D1_19") (pintype "passive"))
    )
    (net (code "51") (name "/PD2") (class "Default")
      (node (ref "IC1") (pin "27") (pinfunction "PD2_27") (pintype "bidirectional"))
      (node (ref "U6") (pin "18") (pinfunction "D2_18") (pintype "passive"))
    )
    (net (code "52") (name "/PD3") (class "Default")
      (node (ref "IC1") (pin "28") (pinfunction "PD3_28") (pintype "bidirectional"))
      (node (ref "U6") (pin "17") (pinfunction "D3_17") (pintype "passive"))
    )
    (net (code "53") (name "/PD4") (class "Default")
      (node (ref "IC1") (pin "29") (pinfunction "PD4_29") (pintype "bidirectional"))
      (node (ref "U6") (pin "14") (pinfunction "D4_14") (pintype "passive"))
    )
    (net (code "54") (name "/PD5") (class "Default")
      (node (ref "IC1") (pin "30") (pinfunction "PD5_30") (pintype "bidirectional"))
      (node (ref "U6") (pin "13") (pinfunction "D5_13") (pintype "passive"))
    )
    (net (code "55") (name "/PD6") (class "Default")
      (node (ref "IC1") (pin "31") (pinfunction "PD6_31") (pintype "bidirectional"))
      (node (ref "U6") (pin "12") (pinfunction "D6_12") (pintype "passive"))
    )
    (net (code "56") (name "/PD7") (class "Default")
      (node (ref "IC1") (pin "32") (pinfunction "PD7_32") (pintype "bidirectional"))
      (node (ref "U6") (pin "11") (pinfunction "D7(MSB)_11") (pintype "passive"))
    )
    (net (code "57") (name "/PE0") (class "Default")
      (node (ref "IC1") (pin "35") (pinfunction "PE0_35") (pintype "bidirectional"))
      (node (ref "U7") (pin "20") (pinfunction "D0(LSB)_20") (pintype "passive"))
    )
    (net (code "58") (name "/PE1") (class "Default")
      (node (ref "IC1") (pin "36") (pinfunction "PE1_36") (pintype "bidirectional"))
      (node (ref "U7") (pin "19") (pinfunction "D1_19") (pintype "passive"))
    )
    (net (code "59") (name "/PE2") (class "Default")
      (node (ref "IC1") (pin "37") (pinfunction "PE2_37") (pintype "bidirectional"))
      (node (ref "U7") (pin "18") (pinfunction "D2_18") (pintype "passive"))
    )
    (net (code "60") (name "/PE3") (class "Default")
      (node (ref "IC1") (pin "38") (pinfunction "PE3_38") (pintype "bidirectional"))
      (node (ref "U7") (pin "17") (pinfunction "D3_17") (pintype "passive"))
    )
    (net (code "61") (name "/PE4") (class "Default")
      (node (ref "IC1") (pin "39") (pinfunction "PE4_39") (pintype "bidirectional"))
      (node (ref "U7") (pin "14") (pinfunction "D4_14") (pintype "passive"))
    )
    (net (code "62") (name "/PE5") (class "Default")
      (node (ref "IC1") (pin "40") (pinfunction "PE5_40") (pintype "bidirectional"))
      (node (ref "U7") (pin "13") (pinfunction "D5_13") (pintype "passive"))
    )
    (net (code "63") (name "/PE6") (class "Default")
      (node (ref "IC1") (pin "41") (pinfunction "PE6_41") (pintype "bidirectional"))
      (node (ref "U7") (pin "12") (pinfunction "D6_12") (pintype "passive"))
    )
    (net (code "64") (name "/PE7") (class "Default")
      (node (ref "IC1") (pin "42") (pinfunction "PE7_42") (pintype "bidirectional"))
      (node (ref "U7") (pin "11") (pinfunction "D7(MSB)_11") (pintype "passive"))
    )
    (net (code "65") (name "/PF0") (class "Default")
      (node (ref "IC1") (pin "45") (pinfunction "PF0_45") (pintype "bidirectional"))
      (node (ref "U4") (pin "15") (pinfunction "A0_15") (pintype "passive"))
    )
    (net (code "66") (name "/PF1") (class "Default")
      (node (ref "IC1") (pin "46") (pinfunction "PF1_46") (pintype "bidirectional"))
      (node (ref "U4") (pin "16") (pinfunction "A1_16") (pintype "passive"))
    )
    (net (code "67") (name "/PF2") (class "Default")
      (node (ref "IC1") (pin "47") (pinfunction "PF2_47") (pintype "bidirectional"))
      (node (ref "U4") (pin "17") (pinfunction "A2_17") (pintype "passive"))
    )
    (net (code "68") (name "/PF3") (class "Default")
      (node (ref "IC1") (pin "48") (pinfunction "PF3_48") (pintype "bidirectional"))
      (node (ref "U4") (pin "18") (pinfunction "A3_18") (pintype "passive"))
    )
    (net (code "69") (name "/PF4") (class "Default")
      (node (ref "IC1") (pin "49") (pinfunction "PF4_49") (pintype "bidirectional"))
      (node (ref "U4") (pin "19") (pinfunction "CSA*_19") (pintype "passive"))
    )
    (net (code "70") (name "/PF5") (class "Default")
      (node (ref "IC1") (pin "50") (pinfunction "PF5_50") (pintype "bidirectional"))
      (node (ref "U4") (pin "20") (pinfunction "CSB*_20") (pintype "passive"))
    )
    (net (code "71") (name "/PF6") (class "Default")
      (node (ref "IC1") (pin "51") (pinfunction "PF6_51") (pintype "bidirectional"))
      (node (ref "U4") (pin "22") (pinfunction "EN*_22") (pintype "passive"))
    )
    (net (code "72") (name "/PF7") (class "Default")
      (node (ref "IC1") (pin "52") (pinfunction "PF7_52") (pintype "bidirectional"))
      (node (ref "U4") (pin "21") (pinfunction "WR*_21") (pintype "passive"))
    )
    (net (code "73") (name "/PH0") (class "Default")
      (node (ref "IC1") (pin "55") (pinfunction "PH0_55") (pintype "bidirectional"))
      (node (ref "U$3") (pin "16") (pinfunction "WE_16") (pintype "bidirectional"))
    )
    (net (code "74") (name "/PH1") (class "Default")
      (node (ref "IC1") (pin "56") (pinfunction "PH1_56") (pintype "bidirectional"))
      (node (ref "U$3") (pin "17") (pinfunction "CAS_17") (pintype "bidirectional"))
    )
    (net (code "75") (name "/PH2") (class "Default")
      (node (ref "IC1") (pin "57") (pinfunction "PH2_57") (pintype "bidirectional"))
      (node (ref "U$3") (pin "18") (pinfunction "RAS_18") (pintype "bidirectional"))
    )
    (net (code "76") (name "/PH3") (class "Default")
      (node (ref "IC1") (pin "58") (pinfunction "PH3_58") (pintype "bidirectional"))
      (node (ref "U$3") (pin "39") (pinfunction "DQM_39") (pintype "bidirectional"))
    )
    (net (code "77") (name "/PH4") (class "Default")
      (node (ref "IC1") (pin "59") (pinfunction "PH4_59") (pintype "bidirectional"))
      (node (ref "U$3") (pin "20") (pinfunction "BA0_20") (pintype "bidirectional"))
    )
    (net (code "78") (name "/PH5") (class "Default")
      (node (ref "IC1") (pin "60") (pinfunction "PH5_60") (pintype "bidirectional"))
      (node (ref "U$3") (pin "21") (pinfunction "BA1_21") (pintype "bidirectional"))
    )
    (net (code "79") (name "/PH6") (class "Default")
      (node (ref "IC1") (pin "61") (pinfunction "PH6_61") (pintype "bidirectional"))
      (node (ref "U$3") (pin "37") (pinfunction "CKE_37") (pintype "bidirectional"))
    )
    (net (code "80") (name "/PH7") (class "Default")
      (node (ref "IC1") (pin "62") (pinfunction "PH7_62") (pintype "bidirectional"))
      (node (ref "U$3") (pin "38") (pinfunction "CLK_38") (pintype "bidirectional"))
    )
    (net (code "81") (name "/PJ0") (class "Default")
      (node (ref "IC1") (pin "65") (pinfunction "PJ0_65") (pintype "bidirectional"))
      (node (ref "U$3") (pin "5") (pinfunction "DQ0_5") (pintype "bidirectional"))
    )
    (net (code "82") (name "/PJ1") (class "Default")
      (node (ref "IC1") (pin "66") (pinfunction "PJ1_66") (pintype "bidirectional"))
      (node (ref "U$3") (pin "11") (pinfunction "DQ1_11") (pintype "bidirectional"))
    )
    (net (code "83") (name "/PJ2") (class "Default")
      (node (ref "IC1") (pin "67") (pinfunction "PJ2_67") (pintype "bidirectional"))
      (node (ref "U$3") (pin "44") (pinfunction "DQ2_44") (pintype "bidirectional"))
    )
    (net (code "84") (name "/PJ3") (class "Default")
      (node (ref "IC1") (pin "68") (pinfunction "PJ3_68") (pintype "bidirectional"))
      (node (ref "U$3") (pin "50") (pinfunction "DQ3_50") (pintype "bidirectional"))
    )
    (net (code "85") (name "/PJ4") (class "Default")
      (node (ref "IC1") (pin "69") (pinfunction "PJ4_69") (pintype "bidirectional"))
      (node (ref "U$3") (pin "33") (pinfunction "A8_33") (pintype "bidirectional"))
    )
    (net (code "86") (name "/PJ5") (class "Default")
      (node (ref "IC1") (pin "70") (pinfunction "PJ5_70") (pintype "bidirectional"))
      (node (ref "U$3") (pin "34") (pinfunction "A9_34") (pintype "bidirectional"))
    )
    (net (code "87") (name "/PJ6") (class "Default")
      (node (ref "IC1") (pin "71") (pinfunction "PJ6_71") (pintype "bidirectional"))
      (node (ref "U$3") (pin "22") (pinfunction "A10_22") (pintype "bidirectional"))
    )
    (net (code "88") (name "/PJ7") (class "Default")
      (node (ref "IC1") (pin "72") (pinfunction "PJ7_72") (pintype "bidirectional"))
      (node (ref "U$3") (pin "35") (pinfunction "A11_35") (pintype "bidirectional"))
    )
    (net (code "89") (name "/PK0") (class "Default")
      (node (ref "IC1") (pin "75") (pinfunction "PK0_75") (pintype "bidirectional"))
      (node (ref "U$3") (pin "23") (pinfunction "A0_23") (pintype "bidirectional"))
    )
    (net (code "90") (name "/PK1") (class "Default")
      (node (ref "IC1") (pin "76") (pinfunction "PK1_76") (pintype "bidirectional"))
      (node (ref "U$3") (pin "24") (pinfunction "A1_24") (pintype "bidirectional"))
    )
    (net (code "91") (name "/PK2") (class "Default")
      (node (ref "IC1") (pin "77") (pinfunction "PK2_77") (pintype "bidirectional"))
      (node (ref "U$3") (pin "25") (pinfunction "A2_25") (pintype "bidirectional"))
    )
    (net (code "92") (name "/PK3") (class "Default")
      (node (ref "IC1") (pin "78") (pinfunction "PK3_78") (pintype "bidirectional"))
      (node (ref "U$3") (pin "26") (pinfunction "A3_26") (pintype "bidirectional"))
    )
    (net (code "93") (name "/PK4") (class "Default")
      (node (ref "IC1") (pin "79") (pinfunction "PK4_79") (pintype "bidirectional"))
      (node (ref "U$3") (pin "29") (pinfunction "A4_29") (pintype "bidirectional"))
    )
    (net (code "94") (name "/PK5") (class "Default")
      (node (ref "IC1") (pin "80") (pinfunction "PK5_80") (pintype "bidirectional"))
      (node (ref "U$3") (pin "30") (pinfunction "A5_30") (pintype "bidirectional"))
    )
    (net (code "95") (name "/PK6") (class "Default")
      (node (ref "IC1") (pin "81") (pinfunction "PK6_81") (pintype "bidirectional"))
      (node (ref "U$3") (pin "31") (pinfunction "A6_31") (pintype "bidirectional"))
    )
    (net (code "96") (name "/PK7") (class "Default")
      (node (ref "IC1") (pin "82") (pinfunction "PK7_82") (pintype "bidirectional"))
      (node (ref "U$3") (pin "32") (pinfunction "A7_32") (pintype "bidirectional"))
    )
    (net (code "97") (name "/PQ0") (class "Default")
      (node (ref "IC1") (pin "85") (pinfunction "PQ0_85") (pintype "bidirectional"))
      (node (ref "U6") (pin "10") (pinfunction "ENCODE_10") (pintype "passive"))
    )
    (net (code "98") (name "/PQ1") (class "Default")
      (node (ref "IC1") (pin "86") (pinfunction "PQ1_86") (pintype "bidirectional"))
      (node (ref "U6") (pin "1") (pinfunction "PWRDWN_1") (pintype "passive"))
    )
    (net (code "99") (name "/PQ2") (class "Default")
      (node (ref "IC1") (pin "87") (pinfunction "PQ2_87") (pintype "bidirectional"))
      (node (ref "U7") (pin "10") (pinfunction "ENCODE_10") (pintype "passive"))
    )
    (net (code "100") (name "/PQ3") (class "Default")
      (node (ref "IC1") (pin "88") (pinfunction "PQ3_88") (pintype "bidirectional"))
      (node (ref "U7") (pin "1") (pinfunction "PWRDWN_1") (pintype "passive"))
    )
    (net (code "101") (name "/READBIN0") (class "Default")
      (node (ref "JP3") (pin "26") (pinfunction "26_26") (pintype "passive"))
    )
    (net (code "102") (name "/RXD0") (class "Default")
      (node (ref "IC1") (pin "17") (pinfunction "PC2_17") (pintype "bidirectional"))
      (node (ref "JP5") (pin "2") (pinfunction "2_2") (pintype "passive"))
    )
    (net (code "103") (name "/SCK") (class "Default")
      (node (ref "IC1") (pin "22") (pinfunction "PC7_22") (pintype "bidirectional"))
      (node (ref "R7") (pin "1") (pinfunction "1_1") (pintype "passive"))
      (node (ref "U5") (pin "5") (pinfunction "CLK_5") (pintype "bidirectional"))
    )
    (net (code "104") (name "/SLICEBIN0") (class "Default")
      (node (ref "IC1") (pin "96") (pinfunction "PA1_96") (pintype "bidirectional"))
      (node (ref "JP3") (pin "27") (pinfunction "27_27") (pintype "passive"))
    )
    (net (code "105") (name "/SS") (class "Default")
      (node (ref "IC1") (pin "19") (pinfunction "PC4_19") (pintype "bidirectional"))
      (node (ref "R9") (pin "1") (pinfunction "1_1") (pintype "passive"))
      (node (ref "U5") (pin "1") (pinfunction "CD/DAT3_1") (pintype "bidirectional"))
    )
    (net (code "106") (name "/TXD0") (class "Default")
      (node (ref "IC1") (pin "18") (pinfunction "PC3_18") (pintype "bidirectional"))
      (node (ref "JP4") (pin "2") (pinfunction "2_2") (pintype "passive"))
    )
    (net (code "107") (name "GND") (class "Default")
      (node (ref "C1") (pin "2") (pinfunction "2_2") (pintype "passive"))
      (node (ref "C10") (pin "2") (pinfunction "2_2") (pintype "passive"))
      (node (ref "C11") (pin "2") (pinfunction "2_2") (pintype "passive"))
      (node (ref "C12") (pin "2") (pinfunction "2_2") (pintype "passive"))
      (node (ref "C13") (pin "2") (pinfunction "2_2") (pintype "passive"))
      (node (ref "C14") (pin "1") (pinfunction "1_1") (pintype "passive"))
      (node (ref "C15") (pin "2") (pinfunction "2_2") (pintype "passive"))
      (node (ref "C16") (pin "1") (pinfunction "1_1") (pintype "passive"))
      (node (ref "C17") (pin "1") (pinfunction "1_1") (pintype "passive"))
      (node (ref "C18") (pin "2") (pinfunction "2_2") (pintype "passive"))
      (node (ref "C19") (pin "2") (pinfunction "2_2") (pintype "passive"))
      (node (ref "C2") (pin "2") (pinfunction "2_2") (pintype "passive"))
      (node (ref "C20") (pin "1") (pinfunction "1_1") (pintype "passive"))
      (node (ref "C22") (pin "1") (pinfunction "1_1") (pintype "passive"))
      (node (ref "C24") (pin "1") (pinfunction "1_1") (pintype "passive"))
      (node (ref "C3") (pin "2") (pinfunction "2_2") (pintype "passive"))
      (node (ref "C4") (pin "2") (pinfunction "2_2") (pintype "passive"))
      (node (ref "C5") (pin "2") (pinfunction "2_2") (pintype "passive"))
      (node (ref "C6") (pin "2") (pinfunction "2_2") (pintype "passive"))
      (node (ref "C7") (pin "2") (pinfunction "2_2") (pintype "passive"))
      (node (ref "C8") (pin "2") (pinfunction "2_2") (pintype "passive"))
      (node (ref "C9") (pin "2") (pinfunction "2_2") (pintype "passive"))
      (node (ref "CN1") (pin "1") (pinfunction "DB0_1") (pintype "passive"))
      (node (ref "CN1") (pin "2") (pinfunction "DB1_2") (pintype "passive"))
      (node (ref "CN1") (pin "21") (pinfunction "IM3_21") (pintype "passive"))
      (node (ref "CN1") (pin "22") (pinfunction "DB4_22") (pintype "passive"))
      (node (ref "CN1") (pin "3") (pinfunction "DB2_3") (pintype "passive"))
      (node (ref "CN1") (pin "34") (pinfunction "GND_34") (pintype "power_in"))
      (node (ref "CN1") (pin "35") (pinfunction "DB5_35") (pintype "passive"))
      (node (ref "CN1") (pin "36") (pinfunction "DB6_36") (pintype "passive"))
      (node (ref "CN1") (pin "37") (pinfunction "DB7_37") (pintype "passive"))
      (node (ref "CN1") (pin "4") (pinfunction "DB3_4") (pintype "passive"))
      (node (ref "CN1") (pin "5") (pinfunction "GND1_5") (pintype "power_in"))
      (node (ref "H1") (pin "B5,5") (pinfunction "MOUNT_B5,5") (pintype "passive"))
      (node (ref "H2") (pin "B5,5") (pinfunction "MOUNT_B5,5") (pintype "passive"))
      (node (ref "H3") (pin "B5,5") (pinfunction "MOUNT_B5,5") (pintype "passive"))
      (node (ref "IC1") (pin "13") (pinfunction "GND1_13") (pintype "bidirectional"))
      (node (ref "IC1") (pin "23") (pinfunction "GND2_23") (pintype "bidirectional"))
      (node (ref "IC1") (pin "3") (pinfunction "AGND_B_3") (pintype "bidirectional"))
      (node (ref "IC1") (pin "33") (pinfunction "GND3_33") (pintype "bidirectional"))
      (node (ref "IC1") (pin "43") (pinfunction "GND4_43") (pintype "bidirectional"))
      (node (ref "IC1") (pin "53") (pinfunction "GND5_53") (pintype "bidirectional"))
      (node (ref "IC1") (pin "63") (pinfunction "GND6_63") (pintype "bidirectional"))
      (node (ref "IC1") (pin "73") (pinfunction "GND7_73") (pintype "bidirectional"))
      (node (ref "IC1") (pin "84") (pinfunction "GND8_84") (pintype "bidirectional"))
      (node (ref "IC1") (pin "93") (pinfunction "AGND_A_93") (pintype "bidirectional"))
      (node (ref "J1") (pin "1") (pinfunction "-_1") (pintype "bidirectional"))
      (node (ref "JP1") (pin "GND") (pinfunction "GND_GND") (pintype "bidirectional"))
      (node (ref "JP2") (pin "4") (pinfunction "4_4") (pintype "passive"))
      (node (ref "JP3") (pin "29") (pinfunction "29_29") (pintype "passive"))
      (node (ref "JP3") (pin "30") (pinfunction "30_30") (pintype "passive"))
      (node (ref "JP7") (pin "6") (pinfunction "6_6") (pintype "passive"))
      (node (ref "Q1") (pin "3") (pinfunction "E_3") (pintype "passive"))
      (node (ref "R1") (pin "1") (pinfunction "1_1") (pintype "passive"))
      (node (ref "R18") (pin "2") (pinfunction "2_2") (pintype "passive"))
      (node (ref "R19") (pin "1") (pinfunction "1_1") (pintype "passive"))
      (node (ref "R20") (pin "1") (pinfunction "1_1") (pintype "passive"))
      (node (ref "R45") (pin "1") (pinfunction "1_1") (pintype "passive"))
      (node (ref "R46") (pin "1") (pinfunction "1_1") (pintype "passive"))
      (node (ref "R47") (pin "1") (pinfunction "1_1") (pintype "passive"))
      (node (ref "R48") (pin "1") (pinfunction "1_1") (pintype "passive"))
      (node (ref "R49") (pin "1") (pinfunction "1_1") (pintype "passive"))
      (node (ref "R50") (pin "1") (pinfunction "1_1") (pintype "passive"))
      (node (ref "R51") (pin "1") (pinfunction "1_1") (pintype "passive"))
      (node (ref "R52") (pin "1") (pinfunction "1_1") (pintype "passive"))
      (node (ref "R53") (pin "1") (pinfunction "1_1") (pintype "passive"))
      (node (ref "R54") (pin "1") (pinfunction "1_1") (pintype "passive"))
      (node (ref "R55") (pin "1") (pinfunction "1_1") (pintype "passive"))
      (node (ref "R56") (pin "1") (pinfunction "1_1") (pintype "passive"))
      (node (ref "R57") (pin "1") (pinfunction "1_1") (pintype "passive"))
      (node (ref "R58") (pin "1") (pinfunction "1_1") (pintype "passive"))
      (node (ref "R59") (pin "1") (pinfunction "1_1") (pintype "passive"))
      (node (ref "R60") (pin "1") (pinfunction "1_1") (pintype "passive"))
      (node (ref "R61") (pin "1") (pinfunction "1_1") (pintype "passive"))
      (node (ref "R62") (pin "1") (pinfunction "1_1") (pintype "passive"))
      (node (ref "R63") (pin "1") (pinfunction "1_1") (pintype "passive"))
      (node (ref "R64") (pin "1") (pinfunction "1_1") (pintype "passive"))
      (node (ref "R65") (pin "1") (pinfunction "1_1") (pintype "passive"))
      (node (ref "R66") (pin "1") (pinfunction "1_1") (pintype "passive"))
      (node (ref "R67") (pin "1") (pinfunction "1_1") (pintype "passive"))
      (node (ref "R68") (pin "1") (pinfunction "1_1") (pintype "passive"))
      (node (ref "S1") (pin "3") (pinfunction "3_3") (pintype "passive"))
      (node (ref "S1") (pin "4") (pinfunction "4_4") (pintype "passive"))
      (node (ref "U$3") (pin "12") (pinfunction "VSSQ2_12") (pintype "power_in"))
      (node (ref "U$3") (pin "19") (pinfunction "CS_19") (pintype "bidirectional"))
      (node (ref "U$3") (pin "28") (pinfunction "VSS1_28") (pintype "power_in"))
      (node (ref "U$3") (pin "41") (pinfunction "VSS2_41") (pintype "power_in"))
      (node (ref "U$3") (pin "46") (pinfunction "VSSQ3_46") (pintype "power_in"))
      (node (ref "U$3") (pin "52") (pinfunction "VSSQ4_52") (pintype "power_in"))
      (node (ref "U$3") (pin "54") (pinfunction "VSS3_54") (pintype "power_in"))
      (node (ref "U$3") (pin "6") (pinfunction "VSSQ1_6") (pintype "power_in"))
      (node (ref "U1") (pin "2") (pinfunction "VSS_2") (pintype "power_in"))
      (node (ref "U2") (pin "2") (pinfunction "GND_2") (pintype "input"))
      (node (ref "U3") (pin "18") (pinfunction "GND18_18") (pintype "power_in"))
      (node (ref "U3") (pin "21") (pinfunction "GND21_21") (pintype "power_in"))
      (node (ref "U3") (pin "25") (pinfunction "AGND_25") (pintype "power_in"))
      (node (ref "U3") (pin "26") (pinfunction "TEST_26") (pintype "input"))
      (node (ref "U3") (pin "7") (pinfunction "GND7_7") (pintype "power_in"))
      (node (ref "U4") (pin "23") (pinfunction "GND_23") (pintype "passive"))
      (node (ref "U4") (pin "24") (pinfunction "VSS_24") (pintype "passive"))
      (node (ref "U5") (pin "3") (pinfunction "VSS1_3") (pintype "power_in"))
      (node (ref "U5") (pin "6") (pinfunction "VSS2_6") (pintype "power_in"))
      (node (ref "U5") (pin "SH@1") (pinfunction "SH_SH@1") (pintype "bidirectional"))
      (node (ref "U5") (pin "SH@2") (pinfunction "SH_SH@2") (pintype "bidirectional"))
      (node (ref "U6") (pin "16") (pinfunction "GND_3_16") (pintype "passive"))
      (node (ref "U6") (pin "4") (pinfunction "GND_4") (pintype "passive"))
      (node (ref "U6") (pin "9") (pinfunction "GND_2_9") (pintype "passive"))
      (node (ref "U7") (pin "16") (pinfunction "GND_3_16") (pintype "passive"))
      (node (ref "U7") (pin "4") (pinfunction "GND_4") (pintype "passive"))
      (node (ref "U7") (pin "9") (pinfunction "GND_2_9") (pintype "passive"))
    )
    (net (code "108") (name "Net-(C6-Pad1)") (class "Default")
      (node (ref "C6") (pin "1") (pinfunction "1_1") (pintype "passive"))
      (node (ref "JP8") (pin "3") (pinfunction "3_3") (pintype "passive"))
      (node (ref "R5") (pin "1") (pinfunction "1_1") (pintype "passive"))
      (node (ref "S1") (pin "1") (pinfunction "1_1") (pintype "passive"))
      (node (ref "S1") (pin "2") (pinfunction "2_2") (pintype "passive"))
    )
    (net (code "109") (name "Net-(C21-Pad1)") (class "Default")
      (node (ref "C21") (pin "1") (pinfunction "1_1") (pintype "passive"))
      (node (ref "R19") (pin "2") (pinfunction "2_2") (pintype "passive"))
    )
    (net (code "110") (name "Net-(C23-Pad1)") (class "Default")
      (node (ref "C23") (pin "1") (pinfunction "1_1") (pintype "passive"))
      (node (ref "R20") (pin "2") (pinfunction "2_2") (pintype "passive"))
    )
    (net (code "111") (name "Net-(CN1-LED-K1)") (class "Default")
      (node (ref "CN1") (pin "17") (pinfunction "LED-K1_17") (pintype "passive"))
      (node (ref "R12") (pin "1") (pinfunction "1_1") (pintype "passive"))
    )
    (net (code "112") (name "Net-(CN1-LED-K2)") (class "Default")
      (node (ref "CN1") (pin "18") (pinfunction "LED-K2_18") (pintype "passive"))
      (node (ref "R13") (pin "1") (pinfunction "1_1") (pintype "passive"))
    )
    (net (code "113") (name "Net-(CN1-LED-K3)") (class "Default")
      (node (ref "CN1") (pin "19") (pinfunction "LED-K3_19") (pintype "passive"))
      (node (ref "R14") (pin "1") (pinfunction "1_1") (pintype "passive"))
    )
    (net (code "114") (name "Net-(CN1-LED-K4)") (class "Default")
      (node (ref "CN1") (pin "20") (pinfunction "LED-K4_20") (pintype "passive"))
      (node (ref "R15") (pin "1") (pinfunction "1_1") (pintype "passive"))
    )
    (net (code "115") (name "Net-(D1-PadA)") (class "Default")
      (node (ref "D1") (pin "A") (pinfunction "A_A") (pintype "passive"))
      (node (ref "R2") (pin "1") (pinfunction "1_1") (pintype "passive"))
    )
    (net (code "116") (name "Net-(D2-PadA)") (class "Default")
      (node (ref "D2") (pin "A") (pinfunction "A_A") (pintype "passive"))
      (node (ref "R3") (pin "1") (pinfunction "1_1") (pintype "passive"))
    )
    (net (code "117") (name "Net-(IC1-AVCC_A)") (class "Default")
      (node (ref "IC1") (pin "4") (pinfunction "AVCC_B_4") (pintype "bidirectional"))
      (node (ref "IC1") (pin "94") (pinfunction "AVCC_A_94") (pintype "bidirectional"))
      (node (ref "L1") (pin "1") (pinfunction "1_1") (pintype "passive"))
    )
    (net (code "118") (name "Net-(IC1-PDI_DATA)") (class "Default")
      (node (ref "IC1") (pin "89") (pinfunction "PDI_DATA_89") (pintype "bidirectional"))
      (node (ref "JP7") (pin "1") (pinfunction "1_1") (pintype "passive"))
    )
    (net (code "119") (name "Net-(IC1-PR0)") (class "Default")
      (node (ref "C18") (pin "1") (pinfunction "1_1") (pintype "passive"))
      (node (ref "IC1") (pin "91") (pinfunction "PR0_91") (pintype "bidirectional"))
      (node (ref "Q2") (pin "2") (pinfunction "2_2") (pintype "passive"))
    )
    (net (code "120") (name "Net-(IC1-PR1)") (class "Default")
      (node (ref "C19") (pin "1") (pinfunction "1_1") (pintype "passive"))
      (node (ref "IC1") (pin "92") (pinfunction "PR1_92") (pintype "bidirectional"))
      (node (ref "Q2") (pin "1") (pinfunction "1_1") (pintype "passive"))
    )
    (net (code "121") (name "Net-(IC1-RESET)") (class "Default")
      (node (ref "IC1") (pin "90") (pinfunction "RESET_90") (pintype "bidirectional"))
      (node (ref "JP8") (pin "1") (pinfunction "1_1") (pintype "passive"))
    )
    (net (code "122") (name "Net-(JP3-Pad1)") (class "Default")
      (node (ref "JP3") (pin "1") (pinfunction "1_1") (pintype "passive"))
      (node (ref "R21") (pin "2") (pinfunction "2_2") (pintype "passive"))
    )
    (net (code "123") (name "Net-(JP3-Pad2)") (class "Default")
      (node (ref "JP3") (pin "2") (pinfunction "2_2") (pintype "passive"))
      (node (ref "R22") (pin "2") (pinfunction "2_2") (pintype "passive"))
    )
    (net (code "124") (name "Net-(JP3-Pad3)") (class "Default")
      (node (ref "JP3") (pin "3") (pinfunction "3_3") (pintype "passive"))
      (node (ref "R23") (pin "2") (pinfunction "2_2") (pintype "passive"))
    )
    (net (code "125") (name "Net-(JP3-Pad4)") (class "Default")
      (node (ref "JP3") (pin "4") (pinfunction "4_4") (pintype "passive"))
      (node (ref "R24") (pin "2") (pinfunction "2_2") (pintype "passive"))
    )
    (net (code "126") (name "Net-(JP3-Pad5)") (class "Default")
      (node (ref "JP3") (pin "5") (pinfunction "5_5") (pintype "passive"))
      (node (ref "R25") (pin "2") (pinfunction "2_2") (pintype "passive"))
    )
    (net (code "127") (name "Net-(JP3-Pad6)") (class "Default")
      (node (ref "JP3") (pin "6") (pinfunction "6_6") (pintype "passive"))
      (node (ref "R26") (pin "2") (pinfunction "2_2") (pintype "passive"))
    )
    (net (code "128") (name "Net-(JP3-Pad7)") (class "Default")
      (node (ref "JP3") (pin "7") (pinfunction "7_7") (pintype "passive"))
      (node (ref "R27") (pin "2") (pinfunction "2_2") (pintype "passive"))
    )
    (net (code "129") (name "Net-(JP3-Pad8)") (class "Default")
      (node (ref "JP3") (pin "8") (pinfunction "8_8") (pintype "passive"))
      (node (ref "R28") (pin "2") (pinfunction "2_2") (pintype "passive"))
    )
    (net (code "130") (name "Net-(JP3-Pad9)") (class "Default")
      (node (ref "JP3") (pin "9") (pinfunction "9_9") (pintype "passive"))
      (node (ref "R29") (pin "2") (pinfunction "2_2") (pintype "passive"))
    )
    (net (code "131") (name "Net-(JP3-Pad10)") (class "Default")
      (node (ref "JP3") (pin "10") (pinfunction "10_10") (pintype "passive"))
      (node (ref "R30") (pin "2") (pinfunction "2_2") (pintype "passive"))
    )
    (net (code "132") (name "Net-(JP3-Pad11)") (class "Default")
      (node (ref "JP3") (pin "11") (pinfunction "11_11") (pintype "passive"))
      (node (ref "R31") (pin "2") (pinfunction "2_2") (pintype "passive"))
    )
    (net (code "133") (name "Net-(JP3-Pad12)") (class "Default")
      (node (ref "JP3") (pin "12") (pinfunction "12_12") (pintype "passive"))
      (node (ref "R32") (pin "2") (pinfunction "2_2") (pintype "passive"))
    )
    (net (code "134") (name "Net-(JP3-Pad13)") (class "Default")
      (node (ref "JP3") (pin "13") (pinfunction "13_13") (pintype "passive"))
      (node (ref "R33") (pin "2") (pinfunction "2_2") (pintype "passive"))
    )
    (net (code "135") (name "Net-(JP3-Pad14)") (class "Default")
      (node (ref "JP3") (pin "14") (pinfunction "14_14") (pintype "passive"))
      (node (ref "R34") (pin "2") (pinfunction "2_2") (pintype "passive"))
    )
    (net (code "136") (name "Net-(JP3-Pad15)") (class "Default")
      (node (ref "JP3") (pin "15") (pinfunction "15_15") (pintype "passive"))
      (node (ref "R35") (pin "2") (pinfunction "2_2") (pintype "passive"))
    )
    (net (code "137") (name "Net-(JP3-Pad16)") (class "Default")
      (node (ref "JP3") (pin "16") (pinfunction "16_16") (pintype "passive"))
      (node (ref "R36") (pin "2") (pinfunction "2_2") (pintype "passive"))
    )
    (net (code "138") (name "Net-(JP3-Pad17)") (class "Default")
      (node (ref "JP3") (pin "17") (pinfunction "17_17") (pintype "passive"))
      (node (ref "R37") (pin "2") (pinfunction "2_2") (pintype "passive"))
    )
    (net (code "139") (name "Net-(JP3-Pad18)") (class "Default")
      (node (ref "JP3") (pin "18") (pinfunction "18_18") (pintype "passive"))
      (node (ref "R38") (pin "2") (pinfunction "2_2") (pintype "passive"))
    )
    (net (code "140") (name "Net-(JP3-Pad19)") (class "Default")
      (node (ref "JP3") (pin "19") (pinfunction "19_19") (pintype "passive"))
      (node (ref "R39") (pin "2") (pinfunction "2_2") (pintype "passive"))
    )
    (net (code "141") (name "Net-(JP3-Pad20)") (class "Default")
      (node (ref "JP3") (pin "20") (pinfunction "20_20") (pintype "passive"))
      (node (ref "R40") (pin "2") (pinfunction "2_2") (pintype "passive"))
    )
    (net (code "142") (name "Net-(JP3-Pad21)") (class "Default")
      (node (ref "JP3") (pin "21") (pinfunction "21_21") (pintype "passive"))
      (node (ref "R41") (pin "2") (pinfunction "2_2") (pintype "passive"))
    )
    (net (code "143") (name "Net-(JP3-Pad22)") (class "Default")
      (node (ref "JP3") (pin "22") (pinfunction "22_22") (pintype "passive"))
      (node (ref "R42") (pin "2") (pinfunction "2_2") (pintype "passive"))
    )
    (net (code "144") (name "Net-(JP3-Pad23)") (class "Default")
      (node (ref "JP3") (pin "23") (pinfunction "23_23") (pintype "passive"))
      (node (ref "R43") (pin "2") (pinfunction "2_2") (pintype "passive"))
    )
    (net (code "145") (name "Net-(JP3-Pad24)") (class "Default")
      (node (ref "JP3") (pin "24") (pinfunction "24_24") (pintype "passive"))
      (node (ref "R44") (pin "2") (pinfunction "2_2") (pintype "passive"))
    )
    (net (code "146") (name "Net-(JP7-Pad5)") (class "Default")
      (node (ref "JP7") (pin "5") (pinfunction "5_5") (pintype "passive"))
      (node (ref "JP8") (pin "2") (pinfunction "2_2") (pintype "passive"))
    )
    (net (code "147") (name "Net-(LED2-C)") (class "Default")
      (node (ref "LED1") (pin "C") (pinfunction "C_C") (pintype "passive"))
      (node (ref "LED2") (pin "K") (pinfunction "C_K") (pintype "passive"))
      (node (ref "R4") (pin "1") (pinfunction "1_1") (pintype "passive"))
    )
    (net (code "148") (name "Net-(Q1-B)") (class "Default")
      (node (ref "Q1") (pin "1") (pinfunction "B_1") (pintype "passive"))
      (node (ref "R16") (pin "1") (pinfunction "1_1") (pintype "passive"))
    )
    (net (code "149") (name "Net-(Q1-C)") (class "Default")
      (node (ref "Q1") (pin "2") (pinfunction "C_2") (pintype "passive"))
      (node (ref "R12") (pin "2") (pinfunction "2_2") (pintype "passive"))
      (node (ref "R13") (pin "2") (pinfunction "2_2") (pintype "passive"))
      (node (ref "R14") (pin "2") (pinfunction "2_2") (pintype "passive"))
      (node (ref "R15") (pin "2") (pinfunction "2_2") (pintype "passive"))
    )
    (net (code "150") (name "Net-(U1-PROG)") (class "Default")
      (node (ref "R1") (pin "2") (pinfunction "2_2") (pintype "passive"))
      (node (ref "U1") (pin "5") (pinfunction "PROG_5") (pintype "input"))
    )
    (net (code "151") (name "Net-(U1-STAT)") (class "Default")
      (node (ref "R4") (pin "2") (pinfunction "2_2") (pintype "passive"))
      (node (ref "U1") (pin "1") (pinfunction "STAT_1") (pintype "output"))
    )
    (net (code "152") (name "Net-(U2-OUT)") (class "Default")
      (node (ref "C3") (pin "1") (pinfunction "1_1") (pintype "passive"))
      (node (ref "JP6") (pin "2") (pinfunction "2_2") (pintype "passive"))
      (node (ref "U2") (pin "5") (pinfunction "OUT_5") (pintype "passive"))
    )
    (net (code "153") (name "Net-(U3-3V3OUT)") (class "Default")
      (node (ref "U3") (pin "17") (pinfunction "3V3OUT_17") (pintype "output"))
      (node (ref "U3") (pin "4") (pinfunction "VCCIO_4") (pintype "power_in"))
    )
    (net (code "154") (name "Net-(U3-RXD)") (class "Default")
      (node (ref "JP4") (pin "1") (pinfunction "1_1") (pintype "passive"))
      (node (ref "U3") (pin "5") (pinfunction "RXD_5") (pintype "input"))
    )
    (net (code "155") (name "Net-(U3-RXLED)") (class "Default")
      (node (ref "D1") (pin "C") (pinfunction "C_C") (pintype "passive"))
      (node (ref "U3") (pin "22") (pinfunction "RXLED_22") (pintype "input"))
    )
    (net (code "156") (name "Net-(U3-TXD)") (class "Default")
      (node (ref "JP5") (pin "1") (pinfunction "1_1") (pintype "passive"))
      (node (ref "U3") (pin "1") (pinfunction "TXD_1") (pintype "output"))
    )
    (net (code "157") (name "Net-(U3-TXLED)") (class "Default")
      (node (ref "D2") (pin "C") (pinfunction "C_C") (pintype "passive"))
      (node (ref "U3") (pin "23") (pinfunction "TXLED_23") (pintype "input"))
    )
    (net (code "158") (name "Net-(U4-DA)") (class "Default")
      (node (ref "U4") (pin "43") (pinfunction "DA_43") (pintype "passive"))
      (node (ref "U6") (pin "7") (pinfunction "AIN_7") (pintype "passive"))
    )
    (net (code "159") (name "Net-(U4-DB)") (class "Default")
      (node (ref "U4") (pin "41") (pinfunction "DB_41") (pintype "passive"))
      (node (ref "U7") (pin "7") (pinfunction "AIN_7") (pintype "passive"))
    )
    (net (code "160") (name "Net-(U6-AIN*)") (class "Default")
      (node (ref "C21") (pin "2") (pinfunction "2_2") (pintype "passive"))
      (node (ref "U6") (pin "6") (pinfunction "AIN*_6") (pintype "passive"))
    )
    (net (code "161") (name "Net-(U6-VREFIN)") (class "Default")
      (node (ref "C4") (pin "1") (pinfunction "1_1") (pintype "passive"))
      (node (ref "U6") (pin "2") (pinfunction "VREFOUT_2") (pintype "passive"))
      (node (ref "U6") (pin "3") (pinfunction "VREFIN_3") (pintype "passive"))
    )
    (net (code "162") (name "Net-(U7-AIN*)") (class "Default")
      (node (ref "C23") (pin "2") (pinfunction "2_2") (pintype "passive"))
      (node (ref "U7") (pin "6") (pinfunction "AIN*_6") (pintype "passive"))
    )
    (net (code "163") (name "Net-(U7-VREFIN)") (class "Default")
      (node (ref "C5") (pin "1") (pinfunction "1_1") (pintype "passive"))
      (node (ref "U7") (pin "2") (pinfunction "VREFOUT_2") (pintype "passive"))
      (node (ref "U7") (pin "3") (pinfunction "VREFIN_3") (pintype "passive"))
    )
    (net (code "164") (name "unconnected-(J1-PAD1-PadNC1)") (class "Default")
      (node (ref "J1") (pin "NC1") (pinfunction "PAD1_NC1") (pintype "bidirectional"))
    )
    (net (code "165") (name "unconnected-(J1-PAD2-PadNC2)") (class "Default")
      (node (ref "J1") (pin "NC2") (pinfunction "PAD2_NC2") (pintype "bidirectional"))
    )
    (net (code "166") (name "unconnected-(JP7-Pad3)") (class "Default")
      (node (ref "JP7") (pin "3") (pinfunction "3_3") (pintype "passive"))
    )
    (net (code "167") (name "unconnected-(JP7-Pad4)") (class "Default")
      (node (ref "JP7") (pin "4") (pinfunction "4_4") (pintype "passive"))
    )
    (net (code "168") (name "unconnected-(U$3-NC0-Pad2)") (class "Default")
      (node (ref "U$3") (pin "2") (pinfunction "NC0_2") (pintype "no_connect"))
    )
    (net (code "169") (name "unconnected-(U$3-NC1-Pad4)") (class "Default")
      (node (ref "U$3") (pin "4") (pinfunction "NC1_4") (pintype "no_connect"))
    )
    (net (code "170") (name "unconnected-(U$3-NC2-Pad7)") (class "Default")
      (node (ref "U$3") (pin "7") (pinfunction "NC2_7") (pintype "no_connect"))
    )
    (net (code "171") (name "unconnected-(U$3-NC3-Pad8)") (class "Default")
      (node (ref "U$3") (pin "8") (pinfunction "NC3_8") (pintype "no_connect"))
    )
    (net (code "172") (name "unconnected-(U$3-NC4-Pad10)") (class "Default")
      (node (ref "U$3") (pin "10") (pinfunction "NC4_10") (pintype "no_connect"))
    )
    (net (code "173") (name "unconnected-(U$3-NC5-Pad13)") (class "Default")
      (node (ref "U$3") (pin "13") (pinfunction "NC5_13") (pintype "no_connect"))
    )
    (net (code "174") (name "unconnected-(U$3-NC6-Pad15)") (class "Default")
      (node (ref "U$3") (pin "15") (pinfunction "NC6_15") (pintype "no_connect"))
    )
    (net (code "175") (name "unconnected-(U$3-NC7-Pad36)") (class "Default")
      (node (ref "U$3") (pin "36") (pinfunction "NC7_36") (pintype "no_connect"))
    )
    (net (code "176") (name "unconnected-(U$3-NC8-Pad40)") (class "Default")
      (node (ref "U$3") (pin "40") (pinfunction "NC8_40") (pintype "no_connect"))
    )
    (net (code "177") (name "unconnected-(U$3-NC9-Pad42)") (class "Default")
      (node (ref "U$3") (pin "42") (pinfunction "NC9_42") (pintype "no_connect"))
    )
    (net (code "178") (name "unconnected-(U$3-NC10-Pad45)") (class "Default")
      (node (ref "U$3") (pin "45") (pinfunction "NC10_45") (pintype "no_connect"))
    )
    (net (code "179") (name "unconnected-(U$3-NC11-Pad47)") (class "Default")
      (node (ref "U$3") (pin "47") (pinfunction "NC11_47") (pintype "no_connect"))
    )
    (net (code "180") (name "unconnected-(U$3-NC12-Pad48)") (class "Default")
      (node (ref "U$3") (pin "48") (pinfunction "NC12_48") (pintype "no_connect"))
    )
    (net (code "181") (name "unconnected-(U$3-NC13-Pad51)") (class "Default")
      (node (ref "U$3") (pin "51") (pinfunction "NC13_51") (pintype "no_connect"))
    )
    (net (code "182") (name "unconnected-(U$3-NC14-Pad53)") (class "Default")
      (node (ref "U$3") (pin "53") (pinfunction "NC14_53") (pintype "no_connect"))
    )
    (net (code "183") (name "unconnected-(U2-BP-Pad4)") (class "Default")
      (node (ref "U2") (pin "4") (pinfunction "BP_4") (pintype "input"))
    )
    (net (code "184") (name "unconnected-(U3-CTS-Pad11)") (class "Default")
      (node (ref "U3") (pin "11") (pinfunction "CTS_11") (pintype "input"))
    )
    (net (code "185") (name "unconnected-(U3-DCD-Pad10)") (class "Default")
      (node (ref "U3") (pin "10") (pinfunction "DCD_10") (pintype "input"))
    )
    (net (code "186") (name "unconnected-(U3-DSR-Pad9)") (class "Default")
      (node (ref "U3") (pin "9") (pinfunction "DSR_9") (pintype "input"))
    )
    (net (code "187") (name "unconnected-(U3-DTR-Pad2)") (class "Default")
      (node (ref "U3") (pin "2") (pinfunction "DTR_2") (pintype "output"))
    )
    (net (code "188") (name "unconnected-(U3-OSCI-Pad27)") (class "Default")
      (node (ref "U3") (pin "27") (pinfunction "OSCI_27") (pintype "input"))
    )
    (net (code "189") (name "unconnected-(U3-OSCO-Pad28)") (class "Default")
      (node (ref "U3") (pin "28") (pinfunction "OSCO_28") (pintype "output"))
    )
    (net (code "190") (name "unconnected-(U3-PWREN-Pad14)") (class "Default")
      (node (ref "U3") (pin "14") (pinfunction "PWREN_14") (pintype "input"))
    )
    (net (code "191") (name "unconnected-(U3-RESET-Pad19)") (class "Default")
      (node (ref "U3") (pin "19") (pinfunction "RESET_19") (pintype "input"))
    )
    (net (code "192") (name "unconnected-(U3-RI-Pad6)") (class "Default")
      (node (ref "U3") (pin "6") (pinfunction "RI_6") (pintype "input"))
    )
    (net (code "193") (name "unconnected-(U3-RTS-Pad3)") (class "Default")
      (node (ref "U3") (pin "3") (pinfunction "RTS_3") (pintype "output"))
    )
    (net (code "194") (name "unconnected-(U3-SLEEP-Pad12)") (class "Default")
      (node (ref "U3") (pin "12") (pinfunction "SLEEP_12") (pintype "input"))
    )
    (net (code "195") (name "unconnected-(U3-TXDEN-Pad13)") (class "Default")
      (node (ref "U3") (pin "13") (pinfunction "TXDEN_13") (pintype "input"))
    )
    (net (code "196") (name "unconnected-(U4-NC-Pad44)") (class "Default")
      (node (ref "U4") (pin "44") (pinfunction "NC_44") (pintype "passive"))
    )
    (net (code "197") (name "unconnected-(U4-NC_2-Pad42)") (class "Default")
      (node (ref "U4") (pin "42") (pinfunction "NC_2_42") (pintype "passive"))
    )
    (net (code "198") (name "unconnected-(U4-S13A-Pad48)") (class "Default")
      (node (ref "U4") (pin "48") (pinfunction "S13A_48") (pintype "passive"))
    )
    (net (code "199") (name "unconnected-(U4-S13B-Pad37)") (class "Default")
      (node (ref "U4") (pin "37") (pinfunction "S13B_37") (pintype "passive"))
    )
    (net (code "200") (name "unconnected-(U4-S14A-Pad47)") (class "Default")
      (node (ref "U4") (pin "47") (pinfunction "S14A_47") (pintype "passive"))
    )
    (net (code "201") (name "unconnected-(U4-S14B-Pad38)") (class "Default")
      (node (ref "U4") (pin "38") (pinfunction "S14B_38") (pintype "passive"))
    )
    (net (code "202") (name "unconnected-(U4-S15A-Pad46)") (class "Default")
      (node (ref "U4") (pin "46") (pinfunction "S15A_46") (pintype "passive"))
    )
    (net (code "203") (name "unconnected-(U4-S15B-Pad39)") (class "Default")
      (node (ref "U4") (pin "39") (pinfunction "S15B_39") (pintype "passive"))
    )
    (net (code "204") (name "unconnected-(U4-S16A-Pad45)") (class "Default")
      (node (ref "U4") (pin "45") (pinfunction "S16A_45") (pintype "passive"))
    )
    (net (code "205") (name "unconnected-(U4-S16B-Pad40)") (class "Default")
      (node (ref "U4") (pin "40") (pinfunction "S16B_40") (pintype "passive"))
    )
    (net (code "206") (name "unconnected-(U5-DAT1-Pad8)") (class "Default")
      (node (ref "U5") (pin "8") (pinfunction "DAT1_8") (pintype "bidirectional"))
    )
    (net (code "207") (name "unconnected-(U5-DAT2-Pad9)") (class "Default")
      (node (ref "U5") (pin "9") (pinfunction "DAT2_9") (pintype "bidirectional"))
    )
  )
)
